# CDevBoard.net
KiCad netlist of a schematic drawn in EAGLE
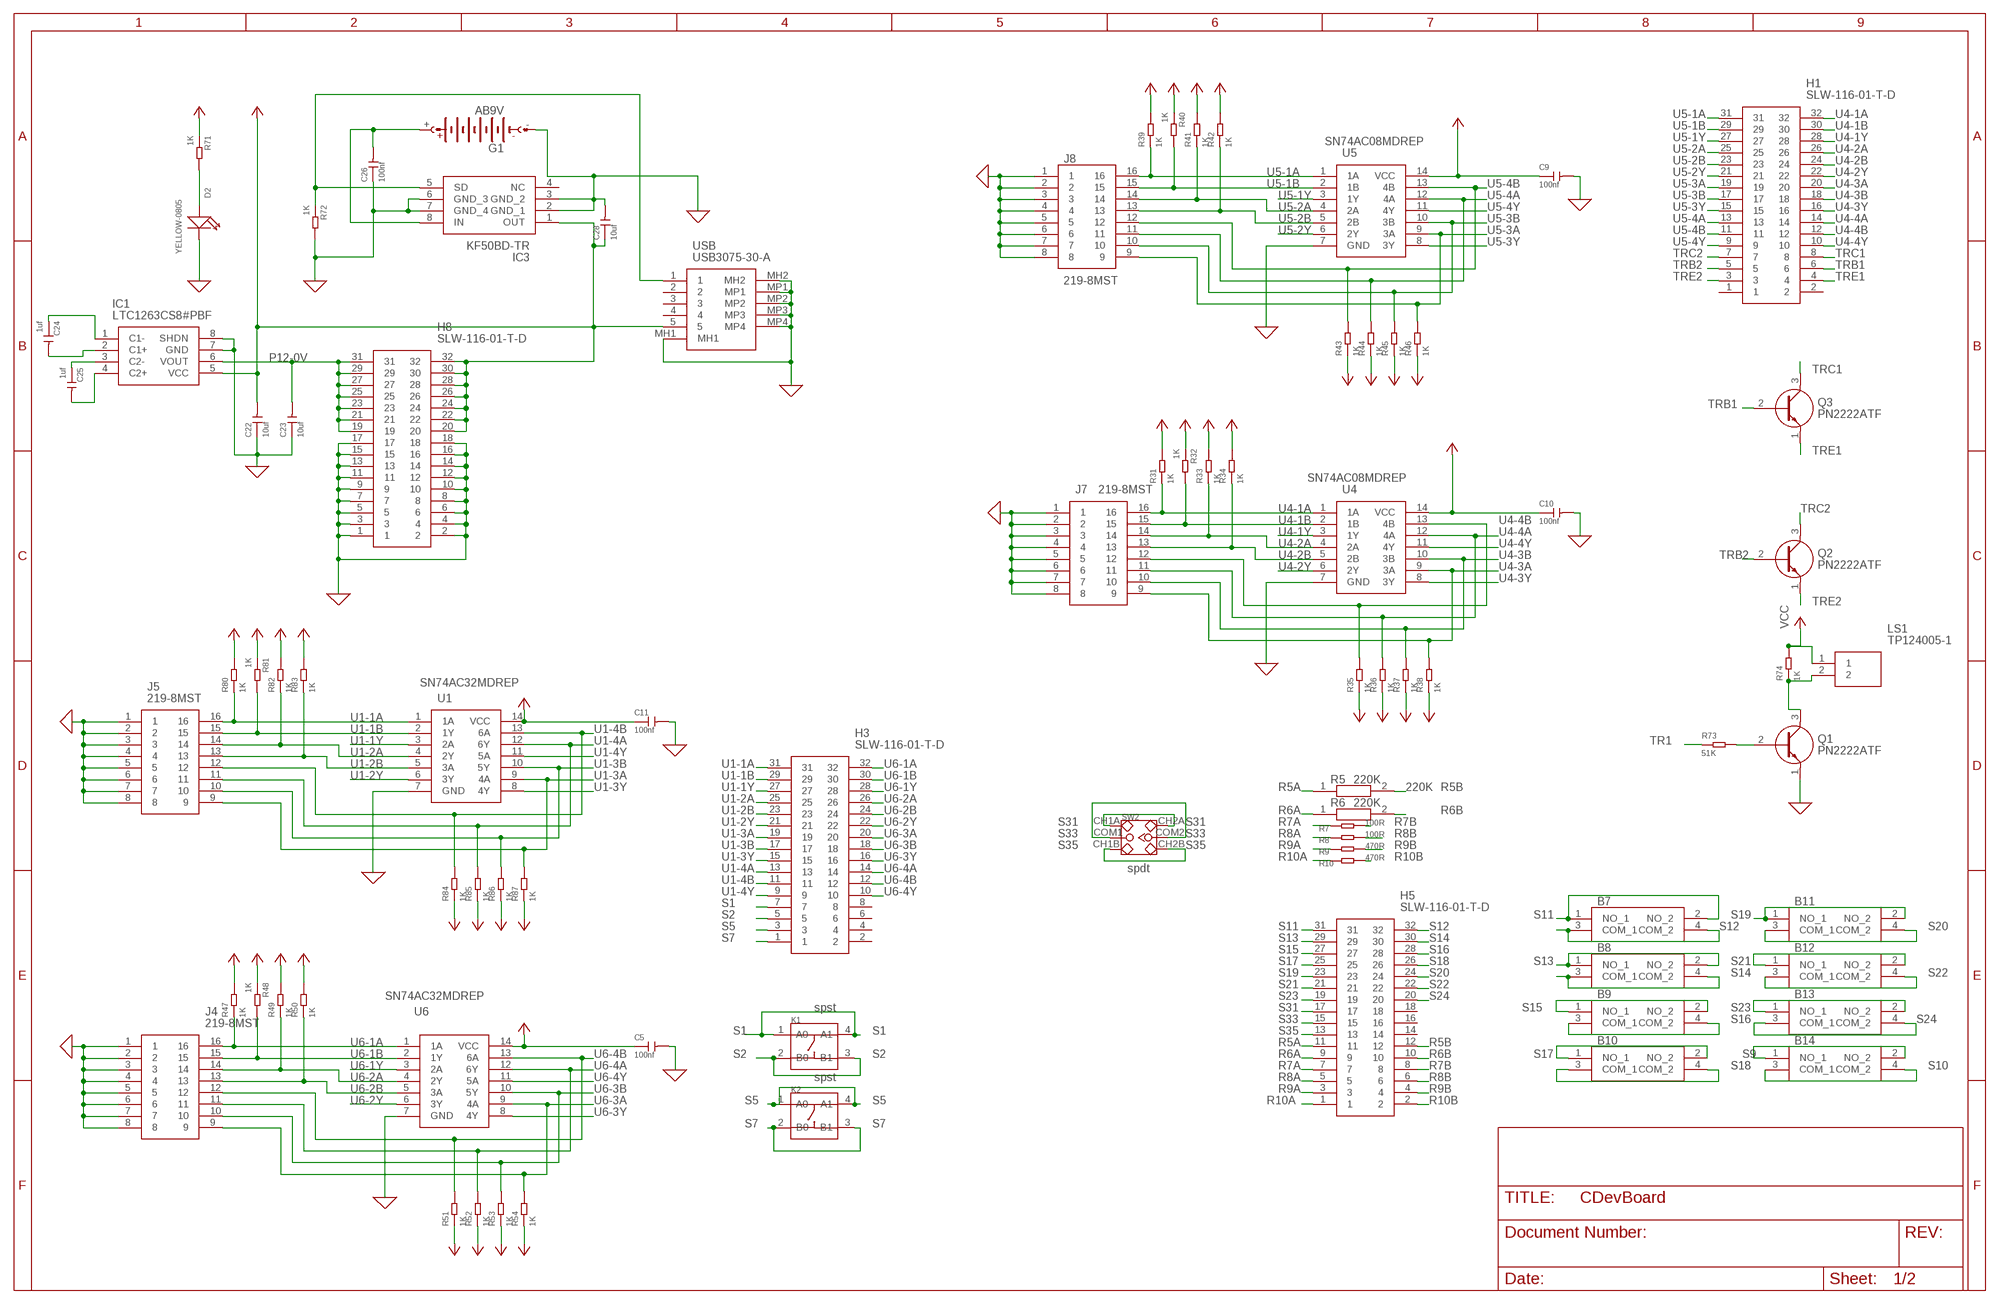
[diagram p0: schematic, sheet 1]
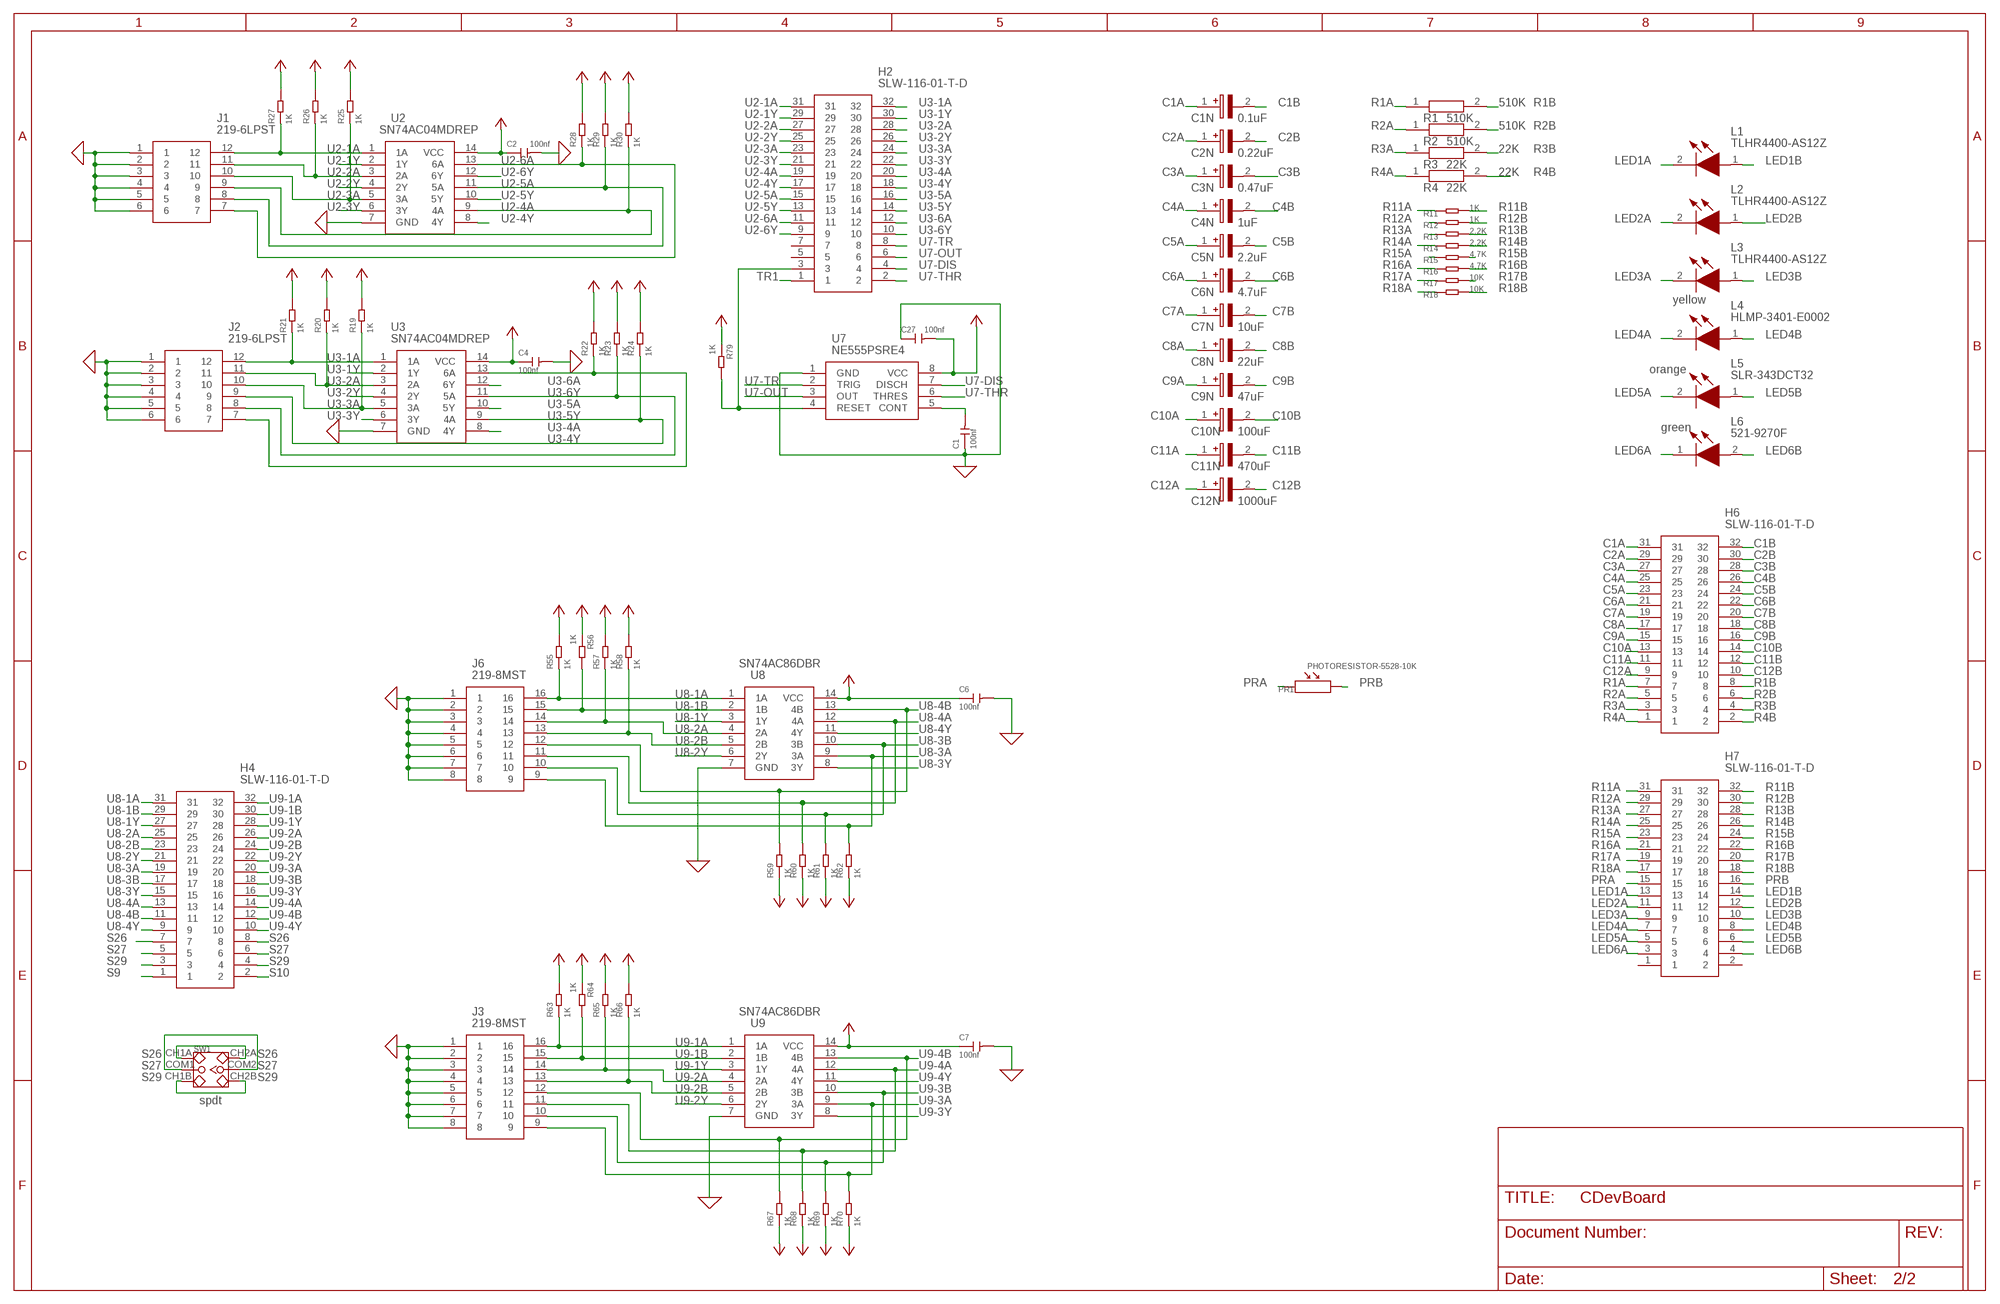
[diagram p1: schematic, sheet 2]

(export (version "E")
  (design (tool "Eeschema 10.0.6"))
  (components
    (comp (ref "B7")
      (value "1301.9317")
      (footprint "eagle-import:13019317")
      (fields (field (name "MOUSER_PART_NUMBER") "693-1301.9317"))
      (libsource (lib "eagle-import") (part "1301.9317"))
    )
    (comp (ref "B8")
      (value "1301.9317")
      (footprint "eagle-import:13019317")
      (fields (field (name "MOUSER_PART_NUMBER") "693-1301.9317"))
      (libsource (lib "eagle-import") (part "1301.9317"))
    )
    (comp (ref "B9")
      (value "1301.9317")
      (footprint "eagle-import:13019317")
      (fields (field (name "MOUSER_PART_NUMBER") "693-1301.9317"))
      (libsource (lib "eagle-import") (part "1301.9317"))
    )
    (comp (ref "B10")
      (value "1301.9317")
      (footprint "eagle-import:13019317")
      (fields (field (name "MOUSER_PART_NUMBER") "693-1301.9317"))
      (libsource (lib "eagle-import") (part "1301.9317"))
    )
    (comp (ref "B11")
      (value "1301.9317")
      (footprint "eagle-import:13019317")
      (fields (field (name "MOUSER_PART_NUMBER") "693-1301.9317"))
      (libsource (lib "eagle-import") (part "1301.9317"))
    )
    (comp (ref "B12")
      (value "1301.9317")
      (footprint "eagle-import:13019317")
      (fields (field (name "MOUSER_PART_NUMBER") "693-1301.9317"))
      (libsource (lib "eagle-import") (part "1301.9317"))
    )
    (comp (ref "B13")
      (value "1301.9317")
      (footprint "eagle-import:13019317")
      (fields (field (name "MOUSER_PART_NUMBER") "693-1301.9317"))
      (libsource (lib "eagle-import") (part "1301.9317"))
    )
    (comp (ref "B14")
      (value "1301.9317")
      (footprint "eagle-import:13019317")
      (fields (field (name "MOUSER_PART_NUMBER") "693-1301.9317"))
      (libsource (lib "eagle-import") (part "1301.9317"))
    )
    (comp (ref "C5")
      (value "100nf")
      (footprint "eagle-import:C0402")
      (fields (field (name "MPN") "CC0402KRX7R8BB104"))
      (libsource (lib "eagle-import") (part "CERAMIC-100NF-25V-10%-X7R(0402)"))
    )
    (comp (ref "C9")
      (value "100nf")
      (footprint "eagle-import:C0402")
      (fields (field (name "MPN") "CC0402KRX7R8BB104"))
      (libsource (lib "eagle-import") (part "CERAMIC-100NF-25V-10%-X7R(0402)"))
    )
    (comp (ref "C10")
      (value "100nf")
      (footprint "eagle-import:C0402")
      (fields (field (name "MPN") "CC0402KRX7R8BB104"))
      (libsource (lib "eagle-import") (part "CERAMIC-100NF-25V-10%-X7R(0402)"))
    )
    (comp (ref "C11")
      (value "100nf")
      (footprint "eagle-import:C0402")
      (fields (field (name "MPN") "CC0402KRX7R8BB104"))
      (libsource (lib "eagle-import") (part "CERAMIC-100NF-25V-10%-X7R(0402)"))
    )
    (comp (ref "C22")
      (value "10uf")
      (footprint "eagle-import:C0805")
      (fields (field (name "MPN") "CC0805KKX5R8BB106"))
      (libsource (lib "eagle-import") (part "CERAMIC-10UF-25V-10%-X5R(0805)"))
    )
    (comp (ref "C23")
      (value "10uf")
      (footprint "eagle-import:C0805")
      (fields (field (name "MPN") "CC0805KKX5R8BB106"))
      (libsource (lib "eagle-import") (part "CERAMIC-10UF-25V-10%-X5R(0805)"))
    )
    (comp (ref "C24")
      (value "1uf")
      (footprint "eagle-import:C0805")
      (fields (field (name "MPN") "CC0805KKX7R8BB105"))
      (libsource (lib "eagle-import") (part "CERAMIC-1UF-25V-10%-X7R(0805)"))
    )
    (comp (ref "C25")
      (value "1uf")
      (footprint "eagle-import:C0805")
      (fields (field (name "MPN") "CC0805KKX7R8BB105"))
      (libsource (lib "eagle-import") (part "CERAMIC-1UF-25V-10%-X7R(0805)"))
    )
    (comp (ref "C26")
      (value "100nf")
      (footprint "eagle-import:C0603")
      (fields (field (name "MPN") "CC0603KRX7R9BB104"))
      (libsource (lib "eagle-import") (part "CERAMIC-100NF-50V-10%-X7R(0603)"))
    )
    (comp (ref "C28")
      (value "10uf")
      (footprint "eagle-import:C0805")
      (fields (field (name "MPN") "CC0805KKX5R8BB106"))
      (libsource (lib "eagle-import") (part "CERAMIC-10UF-25V-10%-X5R(0805)"))
    )
    (comp (ref "D2")
      (value "YELLOW-0805")
      (footprint "eagle-import:LED-0805")
      (fields (field (name "MPN") "17-215UYC/S530-A3/TR8"))
      (libsource (lib "eagle-import") (part "SMD-LED-CLEAR-YELLOW(0805)"))
    )
    (comp (ref "G1")
      (value "AB9V")
      (footprint "eagle-import:AB9V")
      (libsource (lib "eagle-import") (part "AB9V"))
    )
    (comp (ref "H1")
      (value "SLW-116-01-T-D")
      (footprint "eagle-import:SLW-116-01-X")
      (fields (field (name "MOUSER_PART_NUMBER") "200-SLW11601TD"))
      (libsource (lib "eagle-import") (part "SLW-116-01-T-D"))
    )
    (comp (ref "H3")
      (value "SLW-116-01-T-D")
      (footprint "eagle-import:SLW-116-01-X")
      (fields (field (name "MOUSER_PART_NUMBER") "200-SLW11601TD"))
      (libsource (lib "eagle-import") (part "SLW-116-01-T-D"))
    )
    (comp (ref "H5")
      (value "SLW-116-01-T-D")
      (footprint "eagle-import:SLW-116-01-X")
      (fields (field (name "MOUSER_PART_NUMBER") "200-SLW11601TD"))
      (libsource (lib "eagle-import") (part "SLW-116-01-T-D"))
    )
    (comp (ref "H8")
      (value "SLW-116-01-T-D")
      (footprint "eagle-import:SLW-116-01-X")
      (fields (field (name "MOUSER_PART_NUMBER") "200-SLW11601TD"))
      (libsource (lib "eagle-import") (part "SLW-116-01-T-D"))
    )
    (comp (ref "IC1")
      (value "LTC1263CS8#PBF")
      (footprint "eagle-import:SOIC127P599X175-8N")
      (fields (field (name "MOUSER_PART_NUMBER") "584-LTC1263CS8#PBF"))
      (libsource (lib "eagle-import") (part "LTC1263CS8#PBF"))
    )
    (comp (ref "IC3")
      (value "KF50BD-TR")
      (footprint "eagle-import:SOIC127P600X175-8N")
      (description "ST Micro LDO Voltage Regulators 5.0V 0.5A Positive")
      (fields
        (field (name "MANUFACTURER_PART_NUMBER") "LM2936QHBMA-5.0/NOPB")
        (field (name "MOUSER_PART_NUMBER") "595-LM2936QHBMA50NPB")
        (field (name "MANUFACTURER_NAME") "ST Microelectronics")
        (field (name "MANUFACTURER_PART_NUMBER_1") "KF50BD-TR")
        (field (name "MOUSER_PART_NUMBER_1") "511-KF50BD-TR")
        (field (name "MOUSER_PRICE-STOCK") "https://www.mouser.com/ProductDetail/STMicroelectronics/KF50BD-TR?qs=sGAEpiMZZMt1hubY80%2Fs8BMSFdzaUFUoRpw27qJPtVo%3D")
      )
      (libsource (lib "eagle-import") (part "LM2936QHBMA-5.0_NOPB"))
    )
    (comp (ref "J4")
      (value "219-8MST")
      (footprint "eagle-import:2198MST")
      (fields (field (name "MOUSER_PART_NUMBER") "774-2198MST"))
      (libsource (lib "eagle-import") (part "219-8MST"))
    )
    (comp (ref "J5")
      (value "219-8MST")
      (footprint "eagle-import:2198MST")
      (fields (field (name "MOUSER_PART_NUMBER") "774-2198MST"))
      (libsource (lib "eagle-import") (part "219-8MST"))
    )
    (comp (ref "J7")
      (value "219-8MST")
      (footprint "eagle-import:2198MST")
      (fields (field (name "MOUSER_PART_NUMBER") "774-2198MST"))
      (libsource (lib "eagle-import") (part "219-8MST"))
    )
    (comp (ref "J8")
      (value "219-8MST")
      (footprint "eagle-import:2198MST")
      (fields (field (name "MOUSER_PART_NUMBER") "774-2198MST"))
      (libsource (lib "eagle-import") (part "219-8MST"))
    )
    (comp (ref "K1")
      (value "SMD-SWITCH-TACTILE-SPST-NO(4P-D6.0MM)")
      (footprint "eagle-import:SW4-SMD-6.0X6.0X5.0MM")
      (fields (field (name "MPN") "DTSM-62K-S-V-T/R(SN431)") (field (name "TYPE") "spst"))
      (libsource (lib "eagle-import") (part "SMD-SWITCH-TACTILE-SPST-NO(4P-D6.0MM)"))
    )
    (comp (ref "K2")
      (value "SMD-SWITCH-TACTILE-SPST-NO(4P-D6.0MM)")
      (footprint "eagle-import:SW4-SMD-6.0X6.0X5.0MM")
      (fields (field (name "MPN") "DTSM-62K-S-V-T/R(SN431)") (field (name "TYPE") "spst"))
      (libsource (lib "eagle-import") (part "SMD-SWITCH-TACTILE-SPST-NO(4P-D6.0MM)"))
    )
    (comp (ref "LS1")
      (value "TP124005-1")
      (footprint "eagle-import:TP1240051")
      (libsource (lib "eagle-import") (part "TP124005-1"))
    )
    (comp (ref "Q1")
      (value "PN2222ATF")
      (footprint "eagle-import:KA431AZTA")
      (fields (field (name "MOUSER_PART_NUMBER") "512-PN2222ATF"))
      (libsource (lib "eagle-import") (part "PN2222ATF"))
    )
    (comp (ref "Q2")
      (value "PN2222ATF")
      (footprint "eagle-import:KA431AZTA")
      (fields (field (name "MOUSER_PART_NUMBER") "512-PN2222ATF"))
      (libsource (lib "eagle-import") (part "PN2222ATF"))
    )
    (comp (ref "Q3")
      (value "PN2222ATF")
      (footprint "eagle-import:KA431AZTA")
      (fields (field (name "MOUSER_PART_NUMBER") "512-PN2222ATF"))
      (libsource (lib "eagle-import") (part "PN2222ATF"))
    )
    (comp (ref "R5")
      (value "220K")
      (footprint "eagle-import:RESAD1590W60L630D240")
      (fields
        (field (name "MANUFACTURER_PART_NUMBER") "CFR-25JR-52-100R")
        (field (name "MOUSER_PART_NUMBER") "603-CFR-25JR-52100R")
        (field (name "MOUSER_PRICE-STOCK") "https://www.mouser.com/ProductDetail/Yageo/CFR-25JR-52-220K?qs=%2Fha2pyFaduiUclxQMvctpADd0RPeGi7tTMMkrHXtLPwiTqRb%252BoIJFg%3D%3D")
        (field (name "VAL") "220K")
      )
      (libsource (lib "eagle-import") (part "CFR-NEW_CFR-25JR-52-100R"))
    )
    (comp (ref "R6")
      (value "220K")
      (footprint "eagle-import:RESAD1590W60L630D240")
      (fields
        (field (name "MANUFACTURER_PART_NUMBER") "CFR-25JR-52-100R")
        (field (name "MOUSER_PART_NUMBER") "603-CFR-25JR-52100R")
        (field (name "MANUFACTURER_PART_NUMBER_1") "CFR-25JR-52100R")
        (field (name "MOUSER_PRICE-STOCK") "https://www.mouser.com/ProductDetail/Yageo/CFR-25JR-52-220K?qs=%2Fha2pyFaduiUclxQMvctpADd0RPeGi7tTMMkrHXtLPwiTqRb%252BoIJFg%3D%3D")
      )
      (libsource (lib "eagle-import") (part "CFR-25JR-52-100R"))
    )
    (comp (ref "R7")
      (value "100R")
      (footprint "eagle-import:PR-D2.3XL6.5MM")
      (fields (field (name "MPN") "FHCFR-1/4W-101J"))
      (libsource (lib "eagle-import") (part "DIP-RES-100R-5%-1/4W(PR-D2.3XL6.5MM)"))
    )
    (comp (ref "R8")
      (value "100R")
      (footprint "eagle-import:PR-D2.3XL6.5MM")
      (fields (field (name "MPN") "FHCFR-1/4W-101J"))
      (libsource (lib "eagle-import") (part "DIP-RES-100R-5%-1/4W(PR-D2.3XL6.5MM)"))
    )
    (comp (ref "R9")
      (value "470R")
      (footprint "eagle-import:PR-D2.3XL6.5MM")
      (fields (field (name "MPN") "FHCFR-1/4W-471J"))
      (libsource (lib "eagle-import") (part "DIP-RES-470R-5%-1/4W(PR-D2.3XL6.5MM)"))
    )
    (comp (ref "R10")
      (value "470R")
      (footprint "eagle-import:PR-D2.3XL6.5MM")
      (fields (field (name "MPN") "FHCFR-1/4W-471J"))
      (libsource (lib "eagle-import") (part "DIP-RES-470R-5%-1/4W(PR-D2.3XL6.5MM)"))
    )
    (comp (ref "R31")
      (value "1K")
      (footprint "eagle-import:R0805")
      (fields (field (name "MPN") "RC0805JR-071KL"))
      (libsource (lib "eagle-import") (part "SMD-RES-5.1K-1%-1/8W(0805)"))
    )
    (comp (ref "R32")
      (value "1K")
      (footprint "eagle-import:R0805")
      (fields (field (name "MPN") "RC0805JR-071KL"))
      (libsource (lib "eagle-import") (part "SMD-RES-5.1K-1%-1/8W(0805)"))
    )
    (comp (ref "R33")
      (value "1K")
      (footprint "eagle-import:R0805")
      (fields (field (name "MPN") "RC0805JR-071KL"))
      (libsource (lib "eagle-import") (part "SMD-RES-5.1K-1%-1/8W(0805)"))
    )
    (comp (ref "R34")
      (value "1K")
      (footprint "eagle-import:R0805")
      (fields (field (name "MPN") "RC0805JR-071KL"))
      (libsource (lib "eagle-import") (part "SMD-RES-5.1K-1%-1/8W(0805)"))
    )
    (comp (ref "R35")
      (value "1K")
      (footprint "eagle-import:R0805")
      (fields (field (name "MPN") "RC0805JR-071KL"))
      (libsource (lib "eagle-import") (part "SMD-RES-5.1K-1%-1/8W(0805)"))
    )
    (comp (ref "R36")
      (value "1K")
      (footprint "eagle-import:R0805")
      (fields (field (name "MPN") "RC0805JR-071KL"))
      (libsource (lib "eagle-import") (part "SMD-RES-5.1K-1%-1/8W(0805)"))
    )
    (comp (ref "R37")
      (value "1K")
      (footprint "eagle-import:R0805")
      (fields (field (name "MPN") "RC0805JR-071KL"))
      (libsource (lib "eagle-import") (part "SMD-RES-5.1K-1%-1/8W(0805)"))
    )
    (comp (ref "R38")
      (value "1K")
      (footprint "eagle-import:R0805")
      (fields (field (name "MPN") "RC0805JR-071KL"))
      (libsource (lib "eagle-import") (part "SMD-RES-5.1K-1%-1/8W(0805)"))
    )
    (comp (ref "R39")
      (value "1K")
      (footprint "eagle-import:R0805")
      (fields (field (name "MPN") "RC0805JR-071KL"))
      (libsource (lib "eagle-import") (part "SMD-RES-5.1K-1%-1/8W(0805)"))
    )
    (comp (ref "R40")
      (value "1K")
      (footprint "eagle-import:R0805")
      (fields (field (name "MPN") "RC0805JR-071KL"))
      (libsource (lib "eagle-import") (part "SMD-RES-5.1K-1%-1/8W(0805)"))
    )
    (comp (ref "R41")
      (value "1K")
      (footprint "eagle-import:R0805")
      (fields (field (name "MPN") "RC0805JR-071KL"))
      (libsource (lib "eagle-import") (part "SMD-RES-5.1K-1%-1/8W(0805)"))
    )
    (comp (ref "R42")
      (value "1K")
      (footprint "eagle-import:R0805")
      (fields (field (name "MPN") "RC0805JR-071KL"))
      (libsource (lib "eagle-import") (part "SMD-RES-5.1K-1%-1/8W(0805)"))
    )
    (comp (ref "R43")
      (value "1K")
      (footprint "eagle-import:R0805")
      (fields (field (name "MPN") "RC0805JR-071KL"))
      (libsource (lib "eagle-import") (part "SMD-RES-5.1K-1%-1/8W(0805)"))
    )
    (comp (ref "R44")
      (value "1K")
      (footprint "eagle-import:R0805")
      (fields (field (name "MPN") "RC0805JR-071KL"))
      (libsource (lib "eagle-import") (part "SMD-RES-5.1K-1%-1/8W(0805)"))
    )
    (comp (ref "R45")
      (value "1K")
      (footprint "eagle-import:R0805")
      (fields (field (name "MPN") "RC0805JR-071KL"))
      (libsource (lib "eagle-import") (part "SMD-RES-5.1K-1%-1/8W(0805)"))
    )
    (comp (ref "R46")
      (value "1K")
      (footprint "eagle-import:R0805")
      (fields (field (name "MPN") "RC0805JR-071KL"))
      (libsource (lib "eagle-import") (part "SMD-RES-5.1K-1%-1/8W(0805)"))
    )
    (comp (ref "R47")
      (value "1K")
      (footprint "eagle-import:R0805")
      (fields (field (name "MPN") "RC0805JR-071KL"))
      (libsource (lib "eagle-import") (part "SMD-RES-5.1K-1%-1/8W(0805)"))
    )
    (comp (ref "R48")
      (value "1K")
      (footprint "eagle-import:R0805")
      (fields (field (name "MPN") "RC0805JR-071KL"))
      (libsource (lib "eagle-import") (part "SMD-RES-5.1K-1%-1/8W(0805)"))
    )
    (comp (ref "R49")
      (value "1K")
      (footprint "eagle-import:R0805")
      (fields (field (name "MPN") "RC0805JR-071KL"))
      (libsource (lib "eagle-import") (part "SMD-RES-5.1K-1%-1/8W(0805)"))
    )
    (comp (ref "R50")
      (value "1K")
      (footprint "eagle-import:R0805")
      (fields (field (name "MPN") "RC0805JR-071KL"))
      (libsource (lib "eagle-import") (part "SMD-RES-5.1K-1%-1/8W(0805)"))
    )
    (comp (ref "R51")
      (value "1K")
      (footprint "eagle-import:R0805")
      (fields (field (name "MPN") "RC0805JR-071KL"))
      (libsource (lib "eagle-import") (part "SMD-RES-5.1K-1%-1/8W(0805)"))
    )
    (comp (ref "R52")
      (value "1K")
      (footprint "eagle-import:R0805")
      (fields (field (name "MPN") "RC0805JR-071KL"))
      (libsource (lib "eagle-import") (part "SMD-RES-5.1K-1%-1/8W(0805)"))
    )
    (comp (ref "R53")
      (value "1K")
      (footprint "eagle-import:R0805")
      (fields (field (name "MPN") "RC0805JR-071KL"))
      (libsource (lib "eagle-import") (part "SMD-RES-5.1K-1%-1/8W(0805)"))
    )
    (comp (ref "R54")
      (value "1K")
      (footprint "eagle-import:R0805")
      (fields (field (name "MPN") "RC0805JR-071KL"))
      (libsource (lib "eagle-import") (part "SMD-RES-5.1K-1%-1/8W(0805)"))
    )
    (comp (ref "R71")
      (value "1K")
      (footprint "eagle-import:R0805")
      (fields (field (name "MPN") "RC0805JR-071KL"))
      (libsource (lib "eagle-import") (part "SMD-RES-200R-1%-1/8W(0805)"))
    )
    (comp (ref "R72")
      (value "1K")
      (footprint "eagle-import:R0805")
      (fields (field (name "MPN") "RC0805JR-071KL"))
      (libsource (lib "eagle-import") (part "SMD-RES-5.1K-1%-1/8W(0805)"))
    )
    (comp (ref "R73")
      (value "51K")
      (footprint "eagle-import:R0603")
      (fields (field (name "MPN") "RC0603FR-071K5L"))
      (libsource (lib "eagle-import") (part "SMD-RES-51K-1%-1/10W(0603)"))
    )
    (comp (ref "R74")
      (value "1K")
      (footprint "eagle-import:R0805")
      (fields (field (name "MPN") "RC0805JR-071KL"))
      (libsource (lib "eagle-import") (part "SMD-RES-1K-1%-1/8W(0805)"))
    )
    (comp (ref "R80")
      (value "1K")
      (footprint "eagle-import:R0805")
      (fields (field (name "MPN") "RC0805JR-071KL"))
      (libsource (lib "eagle-import") (part "SMD-RES-5.1K-1%-1/8W(0805)"))
    )
    (comp (ref "R81")
      (value "1K")
      (footprint "eagle-import:R0805")
      (fields (field (name "MPN") "RC0805JR-071KL"))
      (libsource (lib "eagle-import") (part "SMD-RES-5.1K-1%-1/8W(0805)"))
    )
    (comp (ref "R82")
      (value "1K")
      (footprint "eagle-import:R0805")
      (fields (field (name "MPN") "RC0805JR-071KL"))
      (libsource (lib "eagle-import") (part "SMD-RES-5.1K-1%-1/8W(0805)"))
    )
    (comp (ref "R83")
      (value "1K")
      (footprint "eagle-import:R0805")
      (fields (field (name "MPN") "RC0805JR-071KL"))
      (libsource (lib "eagle-import") (part "SMD-RES-5.1K-1%-1/8W(0805)"))
    )
    (comp (ref "R84")
      (value "1K")
      (footprint "eagle-import:R0805")
      (fields (field (name "MPN") "RC0805JR-071KL"))
      (libsource (lib "eagle-import") (part "SMD-RES-5.1K-1%-1/8W(0805)"))
    )
    (comp (ref "R85")
      (value "1K")
      (footprint "eagle-import:R0805")
      (fields (field (name "MPN") "RC0805JR-071KL"))
      (libsource (lib "eagle-import") (part "SMD-RES-5.1K-1%-1/8W(0805)"))
    )
    (comp (ref "R86")
      (value "1K")
      (footprint "eagle-import:R0805")
      (fields (field (name "MPN") "RC0805JR-071KL"))
      (libsource (lib "eagle-import") (part "SMD-RES-5.1K-1%-1/8W(0805)"))
    )
    (comp (ref "R87")
      (value "1K")
      (footprint "eagle-import:R0805")
      (fields (field (name "MPN") "RC0805JR-071KL"))
      (libsource (lib "eagle-import") (part "SMD-RES-5.1K-1%-1/8W(0805)"))
    )
    (comp (ref "SW2")
      (value "DIP-TOGGLE-SWITCH-2CH-(2X3P-2.54)")
      (footprint "eagle-import:SW6-2.54-9.0X3.5X3.2+2.0MM")
      (fields (field (name "MPN") "MS-22D18 G2 ROHS") (field (name "TYPE") "spdt"))
      (libsource (lib "eagle-import") (part "DIP-TOGGLE-SWITCH-2CH-(2X3P-2.54)"))
    )
    (comp (ref "U1")
      (value "SN74AC04MDREP")
      (footprint "eagle-import:SOIC127P600X175-14N")
      (fields
        (field (name "MOUSER_PART_NUMBER") "595-SN74AC04MDREP")
        (field (name "MANUFACTURER_PART_NUMBER") "SN74AC32MDREP")
        (field (name "VAL") "SN74AC32MDREP")
      )
      (libsource (lib "eagle-import") (part "SN74AC04MDREP"))
    )
    (comp (ref "U4")
      (value "SN74AC08MDREP")
      (footprint "eagle-import:SOIC127P600X175-14N")
      (fields (field (name "MOUSER_PART_NUMBER") "595-SN74AC08MDREP"))
      (libsource (lib "eagle-import") (part "SN74AC08MDREP"))
    )
    (comp (ref "U5")
      (value "SN74AC08MDREP")
      (footprint "eagle-import:SOIC127P600X175-14N")
      (fields (field (name "MOUSER_PART_NUMBER") "595-SN74AC08MDREP"))
      (libsource (lib "eagle-import") (part "SN74AC08MDREP"))
    )
    (comp (ref "U6")
      (value "SN74AC04MDREP")
      (footprint "eagle-import:SOIC127P600X175-14N")
      (fields
        (field (name "MOUSER_PART_NUMBER") "595-SN74AC04MDREP")
        (field (name "MANUFACTURER_PART_NUMBER") "SN74AC32MDREP")
        (field (name "VAL") "SN74AC32MDREP")
      )
      (libsource (lib "eagle-import") (part "SN74AC04MDREP"))
    )
    (comp (ref "USB")
      (value "USB3075-30-A")
      (footprint "eagle-import:USB307530A")
      (fields (field (name "MOUSER_PART_NUMBER") "640-USB3075-30-A"))
      (libsource (lib "eagle-import") (part "USB3075-30-A"))
    )
    (comp (ref "C1")
      (value "100nf")
      (footprint "eagle-import:C0402")
      (fields (field (name "MPN") "CC0402KRX7R8BB104"))
      (libsource (lib "eagle-import") (part "CERAMIC-100NF-25V-10%-X7R(0402)"))
    )
    (comp (ref "C1N")
      (value "0.1uF")
      (footprint "eagle-import:CAPPRD200W52D500H1250")
      (fields
        (field (name "MANUFACTURER_PART_NUMBER") "860010672001")
        (field (name "MOUSER_PART_NUMBER") "710-860010672001")
      )
      (libsource (lib "eagle-import") (part "860010672001"))
    )
    (comp (ref "C2")
      (value "100nf")
      (footprint "eagle-import:C0402")
      (fields (field (name "MPN") "CC0402KRX7R8BB104"))
      (libsource (lib "eagle-import") (part "CERAMIC-100NF-25V-10%-X7R(0402)"))
    )
    (comp (ref "C2N")
      (value "0.22uF")
      (footprint "eagle-import:CAPPRD200W52D500H1250")
      (fields
        (field (name "MANUFACTURER_PART_NUMBER") "860010672001")
        (field (name "MOUSER_PART_NUMBER") "710-860010672001")
      )
      (libsource (lib "eagle-import") (part "860010672001"))
    )
    (comp (ref "C3N")
      (value "0.47uF")
      (footprint "eagle-import:CAPPRD200W52D500H1250")
      (fields
        (field (name "MANUFACTURER_PART_NUMBER") "860010672001")
        (field (name "MOUSER_PART_NUMBER") "710-860010672001")
      )
      (libsource (lib "eagle-import") (part "860010672001"))
    )
    (comp (ref "C4")
      (value "100nf")
      (footprint "eagle-import:C0402")
      (fields (field (name "MPN") "CC0402KRX7R8BB104"))
      (libsource (lib "eagle-import") (part "CERAMIC-100NF-25V-10%-X7R(0402)"))
    )
    (comp (ref "C4N")
      (value "1uF")
      (footprint "eagle-import:CAPPRD200W52D500H1250")
      (fields
        (field (name "MANUFACTURER_PART_NUMBER") "860010672001")
        (field (name "MOUSER_PART_NUMBER") "710-860010672001")
      )
      (libsource (lib "eagle-import") (part "860010672001"))
    )
    (comp (ref "C5N")
      (value "2.2uF")
      (footprint "eagle-import:CAPPRD200W52D500H1250")
      (fields
        (field (name "MANUFACTURER_PART_NUMBER") "860020672006")
        (field (name "MOUSER_PART_NUMBER") "710-860020672006")
      )
      (libsource (lib "eagle-import") (part "860020672006"))
    )
    (comp (ref "C6")
      (value "100nf")
      (footprint "eagle-import:C0402")
      (fields (field (name "MPN") "CC0402KRX7R8BB104"))
      (libsource (lib "eagle-import") (part "CERAMIC-100NF-25V-10%-X7R(0402)"))
    )
    (comp (ref "C6N")
      (value "4.7uF")
      (footprint "eagle-import:CAPPRD200W52D500H1250")
      (fields
        (field (name "MANUFACTURER_PART_NUMBER") "860020672006")
        (field (name "MOUSER_PART_NUMBER") "710-860020672006")
      )
      (libsource (lib "eagle-import") (part "860020672006"))
    )
    (comp (ref "C7")
      (value "100nf")
      (footprint "eagle-import:C0402")
      (fields (field (name "MPN") "CC0402KRX7R8BB104"))
      (libsource (lib "eagle-import") (part "CERAMIC-100NF-25V-10%-X7R(0402)"))
    )
    (comp (ref "C7N")
      (value "10uF")
      (footprint "eagle-import:CAPPRD200W50D500H1250")
      (fields
        (field (name "MANUFACTURER_PART_NUMBER") "ESK106M010AC3AA")
        (field (name "MOUSER_PART_NUMBER") "80-ESK106M010AC3AA")
      )
      (libsource (lib "eagle-import") (part "ESK106M010AC3AA"))
    )
    (comp (ref "C8N")
      (value "22uF")
      (footprint "eagle-import:CAPPRD200W52D500H1250")
      (fields (field (name "MANUFACTURER_PART_NUMBER") "860010272003") (field (name "VAL") "22uF"))
      (libsource (lib "eagle-import") (part "860010272003"))
    )
    (comp (ref "C9N")
      (value "47uF")
      (footprint "eagle-import:CAPPRD200W52D500H1250")
      (fields (field (name "MANUFACTURER_PART_NUMBER") "860010272003") (field (name "VAL") "47uF"))
      (libsource (lib "eagle-import") (part "860010272003"))
    )
    (comp (ref "C10N")
      (value "100uF")
      (footprint "eagle-import:CAPPRD200W52D500H1250")
      (fields (field (name "MANUFACTURER_PART_NUMBER") "860010272003"))
      (libsource (lib "eagle-import") (part "860010272003"))
    )
    (comp (ref "C11N")
      (value "470uF")
      (footprint "eagle-import:CAPPRD200W52D500H1250")
      (fields (field (name "MANUFACTURER_PART_NUMBER") "860010272003"))
      (libsource (lib "eagle-import") (part "860010272003"))
    )
    (comp (ref "C12N")
      (value "1000uF")
      (footprint "eagle-import:CAPPRD200W52D500H1250")
      (fields (field (name "MANUFACTURER_PART_NUMBER") "860010272003"))
      (libsource (lib "eagle-import") (part "860010272003"))
    )
    (comp (ref "C27")
      (value "100nf")
      (footprint "eagle-import:C0402")
      (fields (field (name "MPN") "CC0402KRX7R8BB104"))
      (libsource (lib "eagle-import") (part "CERAMIC-100NF-25V-10%-X7R(0402)"))
    )
    (comp (ref "H2")
      (value "SLW-116-01-T-D")
      (footprint "eagle-import:SLW-116-01-X")
      (fields (field (name "MOUSER_PART_NUMBER") "200-SLW11601TD"))
      (libsource (lib "eagle-import") (part "SLW-116-01-T-D"))
    )
    (comp (ref "H4")
      (value "SLW-116-01-T-D")
      (footprint "eagle-import:SLW-116-01-X")
      (fields (field (name "MOUSER_PART_NUMBER") "200-SLW11601TD"))
      (libsource (lib "eagle-import") (part "SLW-116-01-T-D"))
    )
    (comp (ref "H6")
      (value "SLW-116-01-T-D")
      (footprint "eagle-import:SLW-116-01-X")
      (fields (field (name "MOUSER_PART_NUMBER") "200-SLW11601TD"))
      (libsource (lib "eagle-import") (part "SLW-116-01-T-D"))
    )
    (comp (ref "H7")
      (value "SLW-116-01-T-D")
      (footprint "eagle-import:SLW-116-01-X")
      (fields (field (name "MOUSER_PART_NUMBER") "200-SLW11601TD"))
      (libsource (lib "eagle-import") (part "SLW-116-01-T-D"))
    )
    (comp (ref "J1")
      (value "219-6LPST")
      (footprint "eagle-import:2196LPST")
      (fields (field (name "MOUSER_PART_NUMBER") "774-2196LPST"))
      (libsource (lib "eagle-import") (part "219-6LPST"))
    )
    (comp (ref "J2")
      (value "219-6LPST")
      (footprint "eagle-import:2196LPST")
      (fields (field (name "MOUSER_PART_NUMBER") "774-2196LPST"))
      (libsource (lib "eagle-import") (part "219-6LPST"))
    )
    (comp (ref "J3")
      (value "219-8MST")
      (footprint "eagle-import:2198MST")
      (fields (field (name "MOUSER_PART_NUMBER") "774-2198MST"))
      (libsource (lib "eagle-import") (part "219-8MST"))
    )
    (comp (ref "J6")
      (value "219-8MST")
      (footprint "eagle-import:2198MST")
      (fields (field (name "MOUSER_PART_NUMBER") "774-2198MST"))
      (libsource (lib "eagle-import") (part "219-8MST"))
    )
    (comp (ref "L1")
      (value "TLHR4400-AS12Z")
      (footprint "eagle-import:TLHR4400AS12Z")
      (fields (field (name "MOUSER_PART_NUMBER") "78-TLHR4400-AS12Z"))
      (libsource (lib "eagle-import") (part "TLHR4400-AS12Z"))
    )
    (comp (ref "L2")
      (value "TLHR4400-AS12Z")
      (footprint "eagle-import:TLHR4400AS12Z")
      (fields (field (name "MOUSER_PART_NUMBER") "78-TLHR4400-AS12Z"))
      (libsource (lib "eagle-import") (part "TLHR4400-AS12Z"))
    )
    (comp (ref "L3")
      (value "TLHR4400-AS12Z")
      (footprint "eagle-import:TLHR4400AS12Z")
      (fields (field (name "MOUSER_PART_NUMBER") "78-TLHR4400-AS12Z"))
      (libsource (lib "eagle-import") (part "TLHR4400-AS12Z"))
    )
    (comp (ref "L4")
      (value "HLMP-3401-E0002")
      (footprint "eagle-import:HLMP3401E0002")
      (fields (field (name "MOUSER_PART_NUMBER") "630-HLMP-3401-E0002") (field (name "COL") "yellow"))
      (libsource (lib "eagle-import") (part "HLMP-3401-E0002"))
    )
    (comp (ref "L5")
      (value "SLR-343DCT32")
      (footprint "eagle-import:SLR343DCT32")
      (fields (field (name "MOUSER_PART_NUMBER") "755-SLR-343DCT32") (field (name "COL") "orange"))
      (libsource (lib "eagle-import") (part "SLR-343DCT32"))
    )
    (comp (ref "L6")
      (value "521-9270F")
      (footprint "eagle-import:5219270F")
      (fields (field (name "MOUSER_PART_NUMBER") "645-521-9270F") (field (name "COL") "green"))
      (libsource (lib "eagle-import") (part "521-9270F"))
    )
    (comp (ref "PR1")
      (value "PHOTORESISTOR-5528-10K")
      (footprint "eagle-import:SNR2-3.0")
      (libsource (lib "eagle-import") (part "PHOTORESISTOR-5528-10K(2P-5.0X4.2MM)"))
    )
    (comp (ref "R1")
      (value "510K")
      (footprint "eagle-import:RESAD1590W60L630D240")
      (fields
        (field (name "MANUFACTURER_PART_NUMBER") "CFR-25JR-52-100R")
        (field (name "MOUSER_PART_NUMBER") "603-CFR-25JR-52100R")
        (field (name "VAL") "510K")
      )
      (libsource (lib "eagle-import") (part "CFR-25JR-52-100R"))
    )
    (comp (ref "R2")
      (value "510K")
      (footprint "eagle-import:RESAD1590W60L630D240")
      (fields
        (field (name "MANUFACTURER_PART_NUMBER") "CFR-25JR-52-100R")
        (field (name "MOUSER_PART_NUMBER") "603-CFR-25JR-52100R")
        (field (name "VAL") "510K")
      )
      (libsource (lib "eagle-import") (part "CFR-25JR-52-100R"))
    )
    (comp (ref "R3")
      (value "22K")
      (footprint "eagle-import:RESAD1590W60L630D240")
      (fields
        (field (name "MANUFACTURER_PART_NUMBER") "CFR-25JR-52-100R")
        (field (name "MOUSER_PART_NUMBER") "603-CFR-25JR-52100R")
        (field (name "VAL") "22K")
      )
      (libsource (lib "eagle-import") (part "CFR-25JR-52-100R"))
    )
    (comp (ref "R4")
      (value "22K")
      (footprint "eagle-import:RESAD1590W60L630D240")
      (fields
        (field (name "MANUFACTURER_PART_NUMBER") "CFR-25JR-52-100R")
        (field (name "MOUSER_PART_NUMBER") "603-CFR-25JR-52100R")
        (field (name "VAL") "22K")
      )
      (libsource (lib "eagle-import") (part "CFR-25JR-52-100R"))
    )
    (comp (ref "R11")
      (value "1K")
      (footprint "eagle-import:PR-D2.3XL6.5MM")
      (fields (field (name "MPN") "FHCFR-1/4W-102J"))
      (libsource (lib "eagle-import") (part "DIP-RES-1K-5%-1/4W(PR-D2.3XL6.5MM)"))
    )
    (comp (ref "R12")
      (value "1K")
      (footprint "eagle-import:PR-D2.3XL6.5MM")
      (fields (field (name "MPN") "FHCFR-1/4W-102J"))
      (libsource (lib "eagle-import") (part "DIP-RES-1K-5%-1/4W(PR-D2.3XL6.5MM)"))
    )
    (comp (ref "R13")
      (value "2.2K")
      (footprint "eagle-import:PR-D2.3XL6.5MM")
      (fields (field (name "MPN") "FHCFR-1/4W-222J"))
      (libsource (lib "eagle-import") (part "DIP-RES-2.2K-5%-1/4W(PR-D2.3XL6.5MM)"))
    )
    (comp (ref "R14")
      (value "2.2K")
      (footprint "eagle-import:PR-D2.3XL6.5MM")
      (fields (field (name "MPN") "FHCFR-1/4W-222J"))
      (libsource (lib "eagle-import") (part "DIP-RES-2.2K-5%-1/4W(PR-D2.3XL6.5MM)"))
    )
    (comp (ref "R15")
      (value "4.7K")
      (footprint "eagle-import:PR-D2.3XL6.5MM")
      (fields (field (name "MPN") "FHCFR-1/4W-472J"))
      (libsource (lib "eagle-import") (part "DIP-RES-4.7K-5%-1/4W(PR-D2.3XL6.5MM)"))
    )
    (comp (ref "R16")
      (value "4.7K")
      (footprint "eagle-import:PR-D2.3XL6.5MM")
      (fields (field (name "MPN") "FHCFR-1/4W-472J"))
      (libsource (lib "eagle-import") (part "DIP-RES-4.7K-5%-1/4W(PR-D2.3XL6.5MM)"))
    )
    (comp (ref "R17")
      (value "10K")
      (footprint "eagle-import:PR-D2.3XL6.5MM")
      (fields (field (name "MPN") "FHCFR-1/4W-103J"))
      (libsource (lib "eagle-import") (part "DIP-RES-10K-5%-1/4W(PR-D2.3XL6.5MM)"))
    )
    (comp (ref "R18")
      (value "10K")
      (footprint "eagle-import:PR-D2.3XL6.5MM")
      (fields (field (name "MPN") "FHCFR-1/4W-103J"))
      (libsource (lib "eagle-import") (part "DIP-RES-10K-5%-1/4W(PR-D2.3XL6.5MM)"))
    )
    (comp (ref "R19")
      (value "1K")
      (footprint "eagle-import:R0805")
      (fields (field (name "MPN") "RC0805JR-071KL"))
      (libsource (lib "eagle-import") (part "SMD-RES-5.1K-1%-1/8W(0805)"))
    )
    (comp (ref "R20")
      (value "1K")
      (footprint "eagle-import:R0805")
      (fields (field (name "MPN") "RC0805JR-071KL"))
      (libsource (lib "eagle-import") (part "SMD-RES-5.1K-1%-1/8W(0805)"))
    )
    (comp (ref "R21")
      (value "1K")
      (footprint "eagle-import:R0805")
      (fields (field (name "MPN") "RC0805JR-071KL"))
      (libsource (lib "eagle-import") (part "SMD-RES-5.1K-1%-1/8W(0805)"))
    )
    (comp (ref "R22")
      (value "1K")
      (footprint "eagle-import:R0805")
      (fields (field (name "MPN") "RC0805JR-071KL"))
      (libsource (lib "eagle-import") (part "SMD-RES-5.1K-1%-1/8W(0805)"))
    )
    (comp (ref "R23")
      (value "1K")
      (footprint "eagle-import:R0805")
      (fields (field (name "MPN") "RC0805JR-071KL"))
      (libsource (lib "eagle-import") (part "SMD-RES-5.1K-1%-1/8W(0805)"))
    )
    (comp (ref "R24")
      (value "1K")
      (footprint "eagle-import:R0805")
      (fields (field (name "MPN") "RC0805JR-071KL"))
      (libsource (lib "eagle-import") (part "SMD-RES-5.1K-1%-1/8W(0805)"))
    )
    (comp (ref "R25")
      (value "1K")
      (footprint "eagle-import:R0805")
      (fields (field (name "MPN") "RC0805JR-071KL"))
      (libsource (lib "eagle-import") (part "SMD-RES-5.1K-1%-1/8W(0805)"))
    )
    (comp (ref "R26")
      (value "1K")
      (footprint "eagle-import:R0805")
      (fields (field (name "MPN") "RC0805JR-071KL"))
      (libsource (lib "eagle-import") (part "SMD-RES-5.1K-1%-1/8W(0805)"))
    )
    (comp (ref "R27")
      (value "1K")
      (footprint "eagle-import:R0805")
      (fields (field (name "MPN") "RC0805JR-071KL"))
      (libsource (lib "eagle-import") (part "SMD-RES-5.1K-1%-1/8W(0805)"))
    )
    (comp (ref "R28")
      (value "1K")
      (footprint "eagle-import:R0805")
      (fields (field (name "MPN") "RC0805JR-071KL"))
      (libsource (lib "eagle-import") (part "SMD-RES-5.1K-1%-1/8W(0805)"))
    )
    (comp (ref "R29")
      (value "1K")
      (footprint "eagle-import:R0805")
      (fields (field (name "MPN") "RC0805JR-071KL"))
      (libsource (lib "eagle-import") (part "SMD-RES-5.1K-1%-1/8W(0805)"))
    )
    (comp (ref "R30")
      (value "1K")
      (footprint "eagle-import:R0805")
      (fields (field (name "MPN") "RC0805JR-071KL"))
      (libsource (lib "eagle-import") (part "SMD-RES-5.1K-1%-1/8W(0805)"))
    )
    (comp (ref "R55")
      (value "1K")
      (footprint "eagle-import:R0805")
      (fields (field (name "MPN") "RC0805JR-071KL"))
      (libsource (lib "eagle-import") (part "SMD-RES-5.1K-1%-1/8W(0805)"))
    )
    (comp (ref "R56")
      (value "1K")
      (footprint "eagle-import:R0805")
      (fields (field (name "MPN") "RC0805JR-071KL"))
      (libsource (lib "eagle-import") (part "SMD-RES-5.1K-1%-1/8W(0805)"))
    )
    (comp (ref "R57")
      (value "1K")
      (footprint "eagle-import:R0805")
      (fields (field (name "MPN") "RC0805JR-071KL"))
      (libsource (lib "eagle-import") (part "SMD-RES-5.1K-1%-1/8W(0805)"))
    )
    (comp (ref "R58")
      (value "1K")
      (footprint "eagle-import:R0805")
      (fields (field (name "MPN") "RC0805JR-071KL"))
      (libsource (lib "eagle-import") (part "SMD-RES-5.1K-1%-1/8W(0805)"))
    )
    (comp (ref "R59")
      (value "1K")
      (footprint "eagle-import:R0805")
      (fields (field (name "MPN") "RC0805JR-071KL"))
      (libsource (lib "eagle-import") (part "SMD-RES-5.1K-1%-1/8W(0805)"))
    )
    (comp (ref "R60")
      (value "1K")
      (footprint "eagle-import:R0805")
      (fields (field (name "MPN") "RC0805JR-071KL"))
      (libsource (lib "eagle-import") (part "SMD-RES-5.1K-1%-1/8W(0805)"))
    )
    (comp (ref "R61")
      (value "1K")
      (footprint "eagle-import:R0805")
      (fields (field (name "MPN") "RC0805JR-071KL"))
      (libsource (lib "eagle-import") (part "SMD-RES-5.1K-1%-1/8W(0805)"))
    )
    (comp (ref "R62")
      (value "1K")
      (footprint "eagle-import:R0805")
      (fields (field (name "MPN") "RC0805JR-071KL"))
      (libsource (lib "eagle-import") (part "SMD-RES-5.1K-1%-1/8W(0805)"))
    )
    (comp (ref "R63")
      (value "1K")
      (footprint "eagle-import:R0805")
      (fields (field (name "MPN") "RC0805JR-071KL"))
      (libsource (lib "eagle-import") (part "SMD-RES-5.1K-1%-1/8W(0805)"))
    )
    (comp (ref "R64")
      (value "1K")
      (footprint "eagle-import:R0805")
      (fields (field (name "MPN") "RC0805JR-071KL"))
      (libsource (lib "eagle-import") (part "SMD-RES-5.1K-1%-1/8W(0805)"))
    )
    (comp (ref "R65")
      (value "1K")
      (footprint "eagle-import:R0805")
      (fields (field (name "MPN") "RC0805JR-071KL"))
      (libsource (lib "eagle-import") (part "SMD-RES-5.1K-1%-1/8W(0805)"))
    )
    (comp (ref "R66")
      (value "1K")
      (footprint "eagle-import:R0805")
      (fields (field (name "MPN") "RC0805JR-071KL"))
      (libsource (lib "eagle-import") (part "SMD-RES-5.1K-1%-1/8W(0805)"))
    )
    (comp (ref "R67")
      (value "1K")
      (footprint "eagle-import:R0805")
      (fields (field (name "MPN") "RC0805JR-071KL"))
      (libsource (lib "eagle-import") (part "SMD-RES-5.1K-1%-1/8W(0805)"))
    )
    (comp (ref "R68")
      (value "1K")
      (footprint "eagle-import:R0805")
      (fields (field (name "MPN") "RC0805JR-071KL"))
      (libsource (lib "eagle-import") (part "SMD-RES-5.1K-1%-1/8W(0805)"))
    )
    (comp (ref "R69")
      (value "1K")
      (footprint "eagle-import:R0805")
      (fields (field (name "MPN") "RC0805JR-071KL"))
      (libsource (lib "eagle-import") (part "SMD-RES-5.1K-1%-1/8W(0805)"))
    )
    (comp (ref "R70")
      (value "1K")
      (footprint "eagle-import:R0805")
      (fields (field (name "MPN") "RC0805JR-071KL"))
      (libsource (lib "eagle-import") (part "SMD-RES-5.1K-1%-1/8W(0805)"))
    )
    (comp (ref "R79")
      (value "1K")
      (footprint "eagle-import:R0805")
      (fields (field (name "MPN") "RC0805JR-071KL"))
      (libsource (lib "eagle-import") (part "SMD-RES-5.1K-1%-1/8W(0805)"))
    )
    (comp (ref "SW1")
      (value "DIP-TOGGLE-SWITCH-2CH-(2X3P-2.54)")
      (footprint "eagle-import:SW6-2.54-9.0X3.5X3.2+2.0MM")
      (fields (field (name "MPN") "MS-22D18 G2 ROHS") (field (name "TYPE") "spdt"))
      (libsource (lib "eagle-import") (part "DIP-TOGGLE-SWITCH-2CH-(2X3P-2.54)"))
    )
    (comp (ref "U2")
      (value "SN74AC04MDREP")
      (footprint "eagle-import:SOIC127P600X175-14N")
      (fields (field (name "MOUSER_PART_NUMBER") "595-SN74AC04MDREP"))
      (libsource (lib "eagle-import") (part "SN74AC04MDREP"))
    )
    (comp (ref "U3")
      (value "SN74AC04MDREP")
      (footprint "eagle-import:SOIC127P600X175-14N")
      (fields (field (name "MOUSER_PART_NUMBER") "595-SN74AC04MDREP"))
      (libsource (lib "eagle-import") (part "SN74AC04MDREP"))
    )
    (comp (ref "U7")
      (value "NE555PSRE4")
      (footprint "eagle-import:SOIC127P780X200-8N")
      (fields (field (name "MOUSER_PART_NUMBER") "595-NE555PSRE4"))
      (libsource (lib "eagle-import") (part "NE555PSRE4"))
    )
    (comp (ref "U8")
      (value "SN74AC86DBR")
      (footprint "eagle-import:SOP65P780X200-14N")
      (fields (field (name "MOUSER_PART_NUMBER") "595-SN74AC86DBR"))
      (libsource (lib "eagle-import") (part "SN74AC86DBR"))
    )
    (comp (ref "U9")
      (value "SN74AC86DBR")
      (footprint "eagle-import:SOP65P780X200-14N")
      (fields (field (name "MOUSER_PART_NUMBER") "595-SN74AC86DBR"))
      (libsource (lib "eagle-import") (part "SN74AC86DBR"))
    )
  )
  (nets
    (net (code "1") (name "0") (class "Default")
      (node (ref "C1") (pin "1") (pinfunction "1_1") (pintype "passive"))
      (node (ref "C10") (pin "2") (pinfunction "2_2") (pintype "passive"))
      (node (ref "C11") (pin "2") (pinfunction "2_2") (pintype "passive"))
      (node (ref "C2") (pin "2") (pinfunction "2_2") (pintype "passive"))
      (node (ref "C22") (pin "1") (pinfunction "1_1") (pintype "passive"))
      (node (ref "C23") (pin "1") (pinfunction "1_1") (pintype "passive"))
      (node (ref "C26") (pin "1") (pinfunction "1_1") (pintype "passive"))
      (node (ref "C27") (pin "1") (pinfunction "1_1") (pintype "passive"))
      (node (ref "C28") (pin "2") (pinfunction "2_2") (pintype "passive"))
      (node (ref "C4") (pin "2") (pinfunction "2_2") (pintype "passive"))
      (node (ref "C5") (pin "2") (pinfunction "2_2") (pintype "passive"))
      (node (ref "C6") (pin "2") (pinfunction "2_2") (pintype "passive"))
      (node (ref "C7") (pin "2") (pinfunction "2_2") (pintype "passive"))
      (node (ref "C9") (pin "2") (pinfunction "2_2") (pintype "passive"))
      (node (ref "D2") (pin "-") (pinfunction "-_-") (pintype "passive"))
      (node (ref "G1") (pin "-") (pinfunction "-_-") (pintype "passive"))
      (node (ref "H8") (pin "1") (pinfunction "1_1") (pintype "bidirectional"))
      (node (ref "H8") (pin "10") (pinfunction "10_10") (pintype "bidirectional"))
      (node (ref "H8") (pin "11") (pinfunction "11_11") (pintype "bidirectional"))
      (node (ref "H8") (pin "12") (pinfunction "12_12") (pintype "bidirectional"))
      (node (ref "H8") (pin "13") (pinfunction "13_13") (pintype "bidirectional"))
      (node (ref "H8") (pin "14") (pinfunction "14_14") (pintype "bidirectional"))
      (node (ref "H8") (pin "15") (pinfunction "15_15") (pintype "bidirectional"))
      (node (ref "H8") (pin "16") (pinfunction "16_16") (pintype "bidirectional"))
      (node (ref "H8") (pin "17") (pinfunction "17_17") (pintype "bidirectional"))
      (node (ref "H8") (pin "18") (pinfunction "18_18") (pintype "bidirectional"))
      (node (ref "H8") (pin "2") (pinfunction "2_2") (pintype "bidirectional"))
      (node (ref "H8") (pin "3") (pinfunction "3_3") (pintype "bidirectional"))
      (node (ref "H8") (pin "4") (pinfunction "4_4") (pintype "bidirectional"))
      (node (ref "H8") (pin "5") (pinfunction "5_5") (pintype "bidirectional"))
      (node (ref "H8") (pin "6") (pinfunction "6_6") (pintype "bidirectional"))
      (node (ref "H8") (pin "7") (pinfunction "7_7") (pintype "bidirectional"))
      (node (ref "H8") (pin "8") (pinfunction "8_8") (pintype "bidirectional"))
      (node (ref "H8") (pin "9") (pinfunction "9_9") (pintype "bidirectional"))
      (node (ref "IC1") (pin "7") (pinfunction "GND_7") (pintype "bidirectional"))
      (node (ref "IC1") (pin "8") (pinfunction "SHDN_8") (pintype "bidirectional"))
      (node (ref "IC3") (pin "2") (pinfunction "GND_1_2") (pintype "bidirectional"))
      (node (ref "IC3") (pin "3") (pinfunction "GND_2_3") (pintype "bidirectional"))
      (node (ref "IC3") (pin "6") (pinfunction "GND_3_6") (pintype "bidirectional"))
      (node (ref "IC3") (pin "7") (pinfunction "GND_4_7") (pintype "bidirectional"))
      (node (ref "J1") (pin "1") (pinfunction "1_1") (pintype "bidirectional"))
      (node (ref "J1") (pin "2") (pinfunction "2_2") (pintype "bidirectional"))
      (node (ref "J1") (pin "3") (pinfunction "3_3") (pintype "bidirectional"))
      (node (ref "J1") (pin "4") (pinfunction "4_4") (pintype "bidirectional"))
      (node (ref "J1") (pin "5") (pinfunction "5_5") (pintype "bidirectional"))
      (node (ref "J1") (pin "6") (pinfunction "6_6") (pintype "bidirectional"))
      (node (ref "J2") (pin "1") (pinfunction "1_1") (pintype "bidirectional"))
      (node (ref "J2") (pin "2") (pinfunction "2_2") (pintype "bidirectional"))
      (node (ref "J2") (pin "3") (pinfunction "3_3") (pintype "bidirectional"))
      (node (ref "J2") (pin "4") (pinfunction "4_4") (pintype "bidirectional"))
      (node (ref "J2") (pin "5") (pinfunction "5_5") (pintype "bidirectional"))
      (node (ref "J2") (pin "6") (pinfunction "6_6") (pintype "bidirectional"))
      (node (ref "J3") (pin "1") (pinfunction "1_1") (pintype "bidirectional"))
      (node (ref "J3") (pin "2") (pinfunction "2_2") (pintype "bidirectional"))
      (node (ref "J3") (pin "3") (pinfunction "3_3") (pintype "bidirectional"))
      (node (ref "J3") (pin "4") (pinfunction "4_4") (pintype "bidirectional"))
      (node (ref "J3") (pin "5") (pinfunction "5_5") (pintype "bidirectional"))
      (node (ref "J3") (pin "6") (pinfunction "6_6") (pintype "bidirectional"))
      (node (ref "J3") (pin "7") (pinfunction "7_7") (pintype "bidirectional"))
      (node (ref "J3") (pin "8") (pinfunction "8_8") (pintype "bidirectional"))
      (node (ref "J4") (pin "1") (pinfunction "1_1") (pintype "bidirectional"))
      (node (ref "J4") (pin "2") (pinfunction "2_2") (pintype "bidirectional"))
      (node (ref "J4") (pin "3") (pinfunction "3_3") (pintype "bidirectional"))
      (node (ref "J4") (pin "4") (pinfunction "4_4") (pintype "bidirectional"))
      (node (ref "J4") (pin "5") (pinfunction "5_5") (pintype "bidirectional"))
      (node (ref "J4") (pin "6") (pinfunction "6_6") (pintype "bidirectional"))
      (node (ref "J4") (pin "7") (pinfunction "7_7") (pintype "bidirectional"))
      (node (ref "J4") (pin "8") (pinfunction "8_8") (pintype "bidirectional"))
      (node (ref "J5") (pin "1") (pinfunction "1_1") (pintype "bidirectional"))
      (node (ref "J5") (pin "2") (pinfunction "2_2") (pintype "bidirectional"))
      (node (ref "J5") (pin "3") (pinfunction "3_3") (pintype "bidirectional"))
      (node (ref "J5") (pin "4") (pinfunction "4_4") (pintype "bidirectional"))
      (node (ref "J5") (pin "5") (pinfunction "5_5") (pintype "bidirectional"))
      (node (ref "J5") (pin "6") (pinfunction "6_6") (pintype "bidirectional"))
      (node (ref "J5") (pin "7") (pinfunction "7_7") (pintype "bidirectional"))
      (node (ref "J5") (pin "8") (pinfunction "8_8") (pintype "bidirectional"))
      (node (ref "J6") (pin "1") (pinfunction "1_1") (pintype "bidirectional"))
      (node (ref "J6") (pin "2") (pinfunction "2_2") (pintype "bidirectional"))
      (node (ref "J6") (pin "3") (pinfunction "3_3") (pintype "bidirectional"))
      (node (ref "J6") (pin "4") (pinfunction "4_4") (pintype "bidirectional"))
      (node (ref "J6") (pin "5") (pinfunction "5_5") (pintype "bidirectional"))
      (node (ref "J6") (pin "6") (pinfunction "6_6") (pintype "bidirectional"))
      (node (ref "J6") (pin "7") (pinfunction "7_7") (pintype "bidirectional"))
      (node (ref "J6") (pin "8") (pinfunction "8_8") (pintype "bidirectional"))
      (node (ref "J7") (pin "1") (pinfunction "1_1") (pintype "bidirectional"))
      (node (ref "J7") (pin "2") (pinfunction "2_2") (pintype "bidirectional"))
      (node (ref "J7") (pin "3") (pinfunction "3_3") (pintype "bidirectional"))
      (node (ref "J7") (pin "4") (pinfunction "4_4") (pintype "bidirectional"))
      (node (ref "J7") (pin "5") (pinfunction "5_5") (pintype "bidirectional"))
      (node (ref "J7") (pin "6") (pinfunction "6_6") (pintype "bidirectional"))
      (node (ref "J7") (pin "7") (pinfunction "7_7") (pintype "bidirectional"))
      (node (ref "J7") (pin "8") (pinfunction "8_8") (pintype "bidirectional"))
      (node (ref "J8") (pin "1") (pinfunction "1_1") (pintype "bidirectional"))
      (node (ref "J8") (pin "2") (pinfunction "2_2") (pintype "bidirectional"))
      (node (ref "J8") (pin "3") (pinfunction "3_3") (pintype "bidirectional"))
      (node (ref "J8") (pin "4") (pinfunction "4_4") (pintype "bidirectional"))
      (node (ref "J8") (pin "5") (pinfunction "5_5") (pintype "bidirectional"))
      (node (ref "J8") (pin "6") (pinfunction "6_6") (pintype "bidirectional"))
      (node (ref "J8") (pin "7") (pinfunction "7_7") (pintype "bidirectional"))
      (node (ref "J8") (pin "8") (pinfunction "8_8") (pintype "bidirectional"))
      (node (ref "Q1") (pin "1") (pinfunction "E_1") (pintype "bidirectional"))
      (node (ref "R72") (pin "2") (pinfunction "2_2") (pintype "passive"))
      (node (ref "U1") (pin "7") (pinfunction "GND_7") (pintype "bidirectional"))
      (node (ref "U2") (pin "7") (pinfunction "GND_7") (pintype "bidirectional"))
      (node (ref "U3") (pin "7") (pinfunction "GND_7") (pintype "bidirectional"))
      (node (ref "U4") (pin "7") (pinfunction "GND_7") (pintype "bidirectional"))
      (node (ref "U5") (pin "7") (pinfunction "GND_7") (pintype "bidirectional"))
      (node (ref "U6") (pin "7") (pinfunction "GND_7") (pintype "bidirectional"))
      (node (ref "U7") (pin "1") (pinfunction "GND_1") (pintype "power_in"))
      (node (ref "U8") (pin "7") (pinfunction "GND_7") (pintype "bidirectional"))
      (node (ref "U9") (pin "7") (pinfunction "GND_7") (pintype "bidirectional"))
      (node (ref "USB") (pin "MH1") (pinfunction "MH1_MH1") (pintype "bidirectional"))
      (node (ref "USB") (pin "MH2") (pinfunction "MH2_MH2") (pintype "bidirectional"))
      (node (ref "USB") (pin "MP1") (pinfunction "MP1_MP1") (pintype "bidirectional"))
      (node (ref "USB") (pin "MP2") (pinfunction "MP2_MP2") (pintype "bidirectional"))
      (node (ref "USB") (pin "MP3") (pinfunction "MP3_MP3") (pintype "bidirectional"))
      (node (ref "USB") (pin "MP4") (pinfunction "MP4_MP4") (pintype "bidirectional"))
    )
    (net (code "2") (name "C1A") (class "Default")
      (node (ref "C1N") (pin "1") (pinfunction "+_1") (pintype "bidirectional"))
      (node (ref "H6") (pin "31") (pinfunction "31_31") (pintype "bidirectional"))
    )
    (net (code "3") (name "C1B") (class "Default")
      (node (ref "C1N") (pin "2") (pinfunction "-_2") (pintype "bidirectional"))
      (node (ref "H6") (pin "32") (pinfunction "32_32") (pintype "bidirectional"))
    )
    (net (code "4") (name "C2A") (class "Default")
      (node (ref "C2N") (pin "1") (pinfunction "+_1") (pintype "bidirectional"))
      (node (ref "H6") (pin "29") (pinfunction "29_29") (pintype "bidirectional"))
    )
    (net (code "5") (name "C2B") (class "Default")
      (node (ref "C2N") (pin "2") (pinfunction "-_2") (pintype "bidirectional"))
      (node (ref "H6") (pin "30") (pinfunction "30_30") (pintype "bidirectional"))
    )
    (net (code "6") (name "C3A") (class "Default")
      (node (ref "C3N") (pin "1") (pinfunction "+_1") (pintype "bidirectional"))
      (node (ref "H6") (pin "27") (pinfunction "27_27") (pintype "bidirectional"))
    )
    (net (code "7") (name "C3B") (class "Default")
      (node (ref "C3N") (pin "2") (pinfunction "-_2") (pintype "bidirectional"))
      (node (ref "H6") (pin "28") (pinfunction "28_28") (pintype "bidirectional"))
    )
    (net (code "8") (name "C4A") (class "Default")
      (node (ref "C4N") (pin "1") (pinfunction "+_1") (pintype "bidirectional"))
      (node (ref "H6") (pin "25") (pinfunction "25_25") (pintype "bidirectional"))
    )
    (net (code "9") (name "C4B") (class "Default")
      (node (ref "C4N") (pin "2") (pinfunction "-_2") (pintype "bidirectional"))
      (node (ref "H6") (pin "26") (pinfunction "26_26") (pintype "bidirectional"))
    )
    (net (code "10") (name "C5A") (class "Default")
      (node (ref "C5N") (pin "1") (pinfunction "+_1") (pintype "bidirectional"))
      (node (ref "H6") (pin "23") (pinfunction "23_23") (pintype "bidirectional"))
    )
    (net (code "11") (name "C5B") (class "Default")
      (node (ref "C5N") (pin "2") (pinfunction "-_2") (pintype "bidirectional"))
      (node (ref "H6") (pin "24") (pinfunction "24_24") (pintype "bidirectional"))
    )
    (net (code "12") (name "C6A") (class "Default")
      (node (ref "C6N") (pin "1") (pinfunction "+_1") (pintype "bidirectional"))
      (node (ref "H6") (pin "21") (pinfunction "21_21") (pintype "bidirectional"))
    )
    (net (code "13") (name "C6B") (class "Default")
      (node (ref "C6N") (pin "2") (pinfunction "-_2") (pintype "bidirectional"))
      (node (ref "H6") (pin "22") (pinfunction "22_22") (pintype "bidirectional"))
    )
    (net (code "14") (name "C7A") (class "Default")
      (node (ref "C7N") (pin "1") (pinfunction "+_1") (pintype "bidirectional"))
      (node (ref "H6") (pin "19") (pinfunction "19_19") (pintype "bidirectional"))
    )
    (net (code "15") (name "C7B") (class "Default")
      (node (ref "C7N") (pin "2") (pinfunction "-_2") (pintype "bidirectional"))
      (node (ref "H6") (pin "20") (pinfunction "20_20") (pintype "bidirectional"))
    )
    (net (code "16") (name "C8A") (class "Default")
      (node (ref "C8N") (pin "1") (pinfunction "+_1") (pintype "bidirectional"))
      (node (ref "H6") (pin "17") (pinfunction "17_17") (pintype "bidirectional"))
    )
    (net (code "17") (name "C8B") (class "Default")
      (node (ref "C8N") (pin "2") (pinfunction "-_2") (pintype "bidirectional"))
      (node (ref "H6") (pin "18") (pinfunction "18_18") (pintype "bidirectional"))
    )
    (net (code "18") (name "C9A") (class "Default")
      (node (ref "C9N") (pin "1") (pinfunction "+_1") (pintype "bidirectional"))
      (node (ref "H6") (pin "15") (pinfunction "15_15") (pintype "bidirectional"))
    )
    (net (code "19") (name "C9B") (class "Default")
      (node (ref "C9N") (pin "2") (pinfunction "-_2") (pintype "bidirectional"))
      (node (ref "H6") (pin "16") (pinfunction "16_16") (pintype "bidirectional"))
    )
    (net (code "20") (name "C10A") (class "Default")
      (node (ref "C10N") (pin "1") (pinfunction "+_1") (pintype "bidirectional"))
      (node (ref "H6") (pin "13") (pinfunction "13_13") (pintype "bidirectional"))
    )
    (net (code "21") (name "C10B") (class "Default")
      (node (ref "C10N") (pin "2") (pinfunction "-_2") (pintype "bidirectional"))
      (node (ref "H6") (pin "14") (pinfunction "14_14") (pintype "bidirectional"))
    )
    (net (code "22") (name "C11A") (class "Default")
      (node (ref "C11N") (pin "1") (pinfunction "+_1") (pintype "bidirectional"))
      (node (ref "H6") (pin "11") (pinfunction "11_11") (pintype "bidirectional"))
    )
    (net (code "23") (name "C11B") (class "Default")
      (node (ref "C11N") (pin "2") (pinfunction "-_2") (pintype "bidirectional"))
      (node (ref "H6") (pin "12") (pinfunction "12_12") (pintype "bidirectional"))
    )
    (net (code "24") (name "C12A") (class "Default")
      (node (ref "C12N") (pin "1") (pinfunction "+_1") (pintype "bidirectional"))
      (node (ref "H6") (pin "9") (pinfunction "9_9") (pintype "bidirectional"))
    )
    (net (code "25") (name "C12B") (class "Default")
      (node (ref "C12N") (pin "2") (pinfunction "-_2") (pintype "bidirectional"))
      (node (ref "H6") (pin "10") (pinfunction "10_10") (pintype "bidirectional"))
    )
    (net (code "26") (name "LED1A") (class "Default")
      (node (ref "H7") (pin "13") (pinfunction "13_13") (pintype "bidirectional"))
      (node (ref "L1") (pin "2") (pinfunction "K_2") (pintype "bidirectional"))
    )
    (net (code "27") (name "LED1B") (class "Default")
      (node (ref "H7") (pin "14") (pinfunction "14_14") (pintype "bidirectional"))
      (node (ref "L1") (pin "1") (pinfunction "A_1") (pintype "bidirectional"))
    )
    (net (code "28") (name "LED2A") (class "Default")
      (node (ref "H7") (pin "11") (pinfunction "11_11") (pintype "bidirectional"))
      (node (ref "L2") (pin "2") (pinfunction "K_2") (pintype "bidirectional"))
    )
    (net (code "29") (name "LED2B") (class "Default")
      (node (ref "H7") (pin "12") (pinfunction "12_12") (pintype "bidirectional"))
      (node (ref "L2") (pin "1") (pinfunction "A_1") (pintype "bidirectional"))
    )
    (net (code "30") (name "LED3A") (class "Default")
      (node (ref "H7") (pin "9") (pinfunction "9_9") (pintype "bidirectional"))
      (node (ref "L3") (pin "2") (pinfunction "K_2") (pintype "bidirectional"))
    )
    (net (code "31") (name "LED3B") (class "Default")
      (node (ref "H7") (pin "10") (pinfunction "10_10") (pintype "bidirectional"))
      (node (ref "L3") (pin "1") (pinfunction "A_1") (pintype "bidirectional"))
    )
    (net (code "32") (name "LED4A") (class "Default")
      (node (ref "H7") (pin "7") (pinfunction "7_7") (pintype "bidirectional"))
      (node (ref "L4") (pin "2") (pinfunction "K_2") (pintype "bidirectional"))
    )
    (net (code "33") (name "LED4B") (class "Default")
      (node (ref "H7") (pin "8") (pinfunction "8_8") (pintype "bidirectional"))
      (node (ref "L4") (pin "1") (pinfunction "A_1") (pintype "bidirectional"))
    )
    (net (code "34") (name "LED5A") (class "Default")
      (node (ref "H7") (pin "5") (pinfunction "5_5") (pintype "bidirectional"))
      (node (ref "L5") (pin "2") (pinfunction "K_2") (pintype "bidirectional"))
    )
    (net (code "35") (name "LED5B") (class "Default")
      (node (ref "H7") (pin "6") (pinfunction "6_6") (pintype "bidirectional"))
      (node (ref "L5") (pin "1") (pinfunction "A_1") (pintype "bidirectional"))
    )
    (net (code "36") (name "LED6A") (class "Default")
      (node (ref "H7") (pin "3") (pinfunction "3_3") (pintype "bidirectional"))
      (node (ref "L6") (pin "1") (pinfunction "K_1") (pintype "bidirectional"))
    )
    (net (code "37") (name "LED6B") (class "Default")
      (node (ref "H7") (pin "4") (pinfunction "4_4") (pintype "bidirectional"))
      (node (ref "L6") (pin "2") (pinfunction "A_2") (pintype "bidirectional"))
    )
    (net (code "38") (name "Net-(D2-Pad+)") (class "Default")
      (node (ref "D2") (pin "+") (pinfunction "+_+") (pintype "passive"))
      (node (ref "R71") (pin "2") (pinfunction "2_2") (pintype "passive"))
    )
    (net (code "39") (name "Net-(IC1-C1+)") (class "Default")
      (node (ref "C24") (pin "2") (pinfunction "2_2") (pintype "passive"))
      (node (ref "IC1") (pin "2") (pinfunction "C1+_2") (pintype "bidirectional"))
    )
    (net (code "40") (name "Net-(IC1-C1-)") (class "Default")
      (node (ref "C24") (pin "1") (pinfunction "1_1") (pintype "passive"))
      (node (ref "IC1") (pin "1") (pinfunction "C1-_1") (pintype "bidirectional"))
    )
    (net (code "41") (name "Net-(IC1-C2+)") (class "Default")
      (node (ref "C25") (pin "2") (pinfunction "2_2") (pintype "passive"))
      (node (ref "IC1") (pin "4") (pinfunction "C2+_4") (pintype "bidirectional"))
    )
    (net (code "42") (name "Net-(IC1-C2-)") (class "Default")
      (node (ref "C25") (pin "1") (pinfunction "1_1") (pintype "passive"))
      (node (ref "IC1") (pin "3") (pinfunction "C2-_3") (pintype "bidirectional"))
    )
    (net (code "43") (name "Net-(IC3-IN)") (class "Default")
      (node (ref "C26") (pin "2") (pinfunction "2_2") (pintype "passive"))
      (node (ref "G1") (pin "+") (pinfunction "+_+") (pintype "passive"))
      (node (ref "IC3") (pin "8") (pinfunction "IN_8") (pintype "bidirectional"))
    )
    (net (code "44") (name "Net-(IC3-SD)") (class "Default")
      (node (ref "IC3") (pin "5") (pinfunction "SD_5") (pintype "bidirectional"))
      (node (ref "R72") (pin "1") (pinfunction "1_1") (pintype "passive"))
      (node (ref "USB") (pin "1") (pinfunction "1_1") (pintype "bidirectional"))
    )
    (net (code "45") (name "Net-(Q1-B)") (class "Default")
      (node (ref "Q1") (pin "2") (pinfunction "B_2") (pintype "bidirectional"))
      (node (ref "R73") (pin "2") (pinfunction "2_2") (pintype "passive"))
    )
    (net (code "46") (name "Net-(Q1-C)") (class "Default")
      (node (ref "LS1") (pin "2") (pinfunction "2_2") (pintype "bidirectional"))
      (node (ref "Q1") (pin "3") (pinfunction "C_3") (pintype "bidirectional"))
      (node (ref "R74") (pin "1") (pinfunction "1_1") (pintype "passive"))
    )
    (net (code "47") (name "Net-(U7-CONT)") (class "Default")
      (node (ref "C1") (pin "2") (pinfunction "2_2") (pintype "passive"))
      (node (ref "U7") (pin "5") (pinfunction "CONT_5") (pintype "bidirectional"))
    )
    (net (code "48") (name "Net-(U7-RESET)") (class "Default")
      (node (ref "H2") (pin "3") (pinfunction "3_3") (pintype "bidirectional"))
      (node (ref "R79") (pin "2") (pinfunction "2_2") (pintype "passive"))
      (node (ref "U7") (pin "4") (pinfunction "RESET_4") (pintype "bidirectional"))
    )
    (net (code "49") (name "P12-0V") (class "Default")
      (node (ref "C23") (pin "2") (pinfunction "2_2") (pintype "passive"))
      (node (ref "H8") (pin "19") (pinfunction "19_19") (pintype "bidirectional"))
      (node (ref "H8") (pin "21") (pinfunction "21_21") (pintype "bidirectional"))
      (node (ref "H8") (pin "23") (pinfunction "23_23") (pintype "bidirectional"))
      (node (ref "H8") (pin "25") (pinfunction "25_25") (pintype "bidirectional"))
      (node (ref "H8") (pin "27") (pinfunction "27_27") (pintype "bidirectional"))
      (node (ref "H8") (pin "29") (pinfunction "29_29") (pintype "bidirectional"))
      (node (ref "H8") (pin "31") (pinfunction "31_31") (pintype "bidirectional"))
      (node (ref "IC1") (pin "6") (pinfunction "VOUT_6") (pintype "bidirectional"))
    )
    (net (code "50") (name "PRA") (class "Default")
      (node (ref "H7") (pin "15") (pinfunction "15_15") (pintype "bidirectional"))
      (node (ref "PR1") (pin "1") (pinfunction "P$1_1") (pintype "bidirectional"))
    )
    (net (code "51") (name "PRB") (class "Default")
      (node (ref "H7") (pin "16") (pinfunction "16_16") (pintype "bidirectional"))
      (node (ref "PR1") (pin "2") (pinfunction "P$2_2") (pintype "bidirectional"))
    )
    (net (code "52") (name "R1A") (class "Default")
      (node (ref "H6") (pin "7") (pinfunction "7_7") (pintype "bidirectional"))
      (node (ref "R1") (pin "1") (pinfunction "1_1") (pintype "bidirectional"))
    )
    (net (code "53") (name "R1B") (class "Default")
      (node (ref "H6") (pin "8") (pinfunction "8_8") (pintype "bidirectional"))
      (node (ref "R1") (pin "2") (pinfunction "2_2") (pintype "bidirectional"))
    )
    (net (code "54") (name "R2A") (class "Default")
      (node (ref "H6") (pin "5") (pinfunction "5_5") (pintype "bidirectional"))
      (node (ref "R2") (pin "1") (pinfunction "1_1") (pintype "bidirectional"))
    )
    (net (code "55") (name "R2B") (class "Default")
      (node (ref "H6") (pin "6") (pinfunction "6_6") (pintype "bidirectional"))
      (node (ref "R2") (pin "2") (pinfunction "2_2") (pintype "bidirectional"))
    )
    (net (code "56") (name "R3A") (class "Default")
      (node (ref "H6") (pin "3") (pinfunction "3_3") (pintype "bidirectional"))
      (node (ref "R3") (pin "1") (pinfunction "1_1") (pintype "bidirectional"))
    )
    (net (code "57") (name "R3B") (class "Default")
      (node (ref "H6") (pin "4") (pinfunction "4_4") (pintype "bidirectional"))
      (node (ref "R3") (pin "2") (pinfunction "2_2") (pintype "bidirectional"))
    )
    (net (code "58") (name "R4A") (class "Default")
      (node (ref "H6") (pin "1") (pinfunction "1_1") (pintype "bidirectional"))
      (node (ref "R4") (pin "1") (pinfunction "1_1") (pintype "bidirectional"))
    )
    (net (code "59") (name "R4B") (class "Default")
      (node (ref "H6") (pin "2") (pinfunction "2_2") (pintype "bidirectional"))
      (node (ref "R4") (pin "2") (pinfunction "2_2") (pintype "bidirectional"))
    )
    (net (code "60") (name "R5A") (class "Default")
      (node (ref "H5") (pin "11") (pinfunction "11_11") (pintype "bidirectional"))
      (node (ref "R5") (pin "1") (pinfunction "1_1") (pintype "bidirectional"))
    )
    (net (code "61") (name "R5B") (class "Default")
      (node (ref "H5") (pin "12") (pinfunction "12_12") (pintype "bidirectional"))
      (node (ref "R5") (pin "2") (pinfunction "2_2") (pintype "bidirectional"))
    )
    (net (code "62") (name "R6A") (class "Default")
      (node (ref "H5") (pin "9") (pinfunction "9_9") (pintype "bidirectional"))
      (node (ref "R6") (pin "1") (pinfunction "1_1") (pintype "bidirectional"))
    )
    (net (code "63") (name "R6B") (class "Default")
      (node (ref "H5") (pin "10") (pinfunction "10_10") (pintype "bidirectional"))
      (node (ref "R6") (pin "2") (pinfunction "2_2") (pintype "bidirectional"))
    )
    (net (code "64") (name "R7A") (class "Default")
      (node (ref "H5") (pin "7") (pinfunction "7_7") (pintype "bidirectional"))
      (node (ref "R7") (pin "1") (pinfunction "1_1") (pintype "passive"))
    )
    (net (code "65") (name "R7B") (class "Default")
      (node (ref "H5") (pin "8") (pinfunction "8_8") (pintype "bidirectional"))
      (node (ref "R7") (pin "2") (pinfunction "2_2") (pintype "passive"))
    )
    (net (code "66") (name "R8A") (class "Default")
      (node (ref "H5") (pin "5") (pinfunction "5_5") (pintype "bidirectional"))
      (node (ref "R8") (pin "1") (pinfunction "1_1") (pintype "passive"))
    )
    (net (code "67") (name "R8B") (class "Default")
      (node (ref "H5") (pin "6") (pinfunction "6_6") (pintype "bidirectional"))
      (node (ref "R8") (pin "2") (pinfunction "2_2") (pintype "passive"))
    )
    (net (code "68") (name "R9A") (class "Default")
      (node (ref "H5") (pin "3") (pinfunction "3_3") (pintype "bidirectional"))
      (node (ref "R9") (pin "1") (pinfunction "1_1") (pintype "passive"))
    )
    (net (code "69") (name "R9B") (class "Default")
      (node (ref "H5") (pin "4") (pinfunction "4_4") (pintype "bidirectional"))
      (node (ref "R9") (pin "2") (pinfunction "2_2") (pintype "passive"))
    )
    (net (code "70") (name "R10A") (class "Default")
      (node (ref "H5") (pin "1") (pinfunction "1_1") (pintype "bidirectional"))
      (node (ref "R10") (pin "1") (pinfunction "1_1") (pintype "passive"))
    )
    (net (code "71") (name "R10B") (class "Default")
      (node (ref "H5") (pin "2") (pinfunction "2_2") (pintype "bidirectional"))
      (node (ref "R10") (pin "2") (pinfunction "2_2") (pintype "passive"))
    )
    (net (code "72") (name "R11A") (class "Default")
      (node (ref "H7") (pin "31") (pinfunction "31_31") (pintype "bidirectional"))
      (node (ref "R11") (pin "1") (pinfunction "1_1") (pintype "passive"))
    )
    (net (code "73") (name "R11B") (class "Default")
      (node (ref "H7") (pin "32") (pinfunction "32_32") (pintype "bidirectional"))
      (node (ref "R11") (pin "2") (pinfunction "2_2") (pintype "passive"))
    )
    (net (code "74") (name "R12A") (class "Default")
      (node (ref "H7") (pin "29") (pinfunction "29_29") (pintype "bidirectional"))
      (node (ref "R12") (pin "1") (pinfunction "1_1") (pintype "passive"))
    )
    (net (code "75") (name "R12B") (class "Default")
      (node (ref "H7") (pin "30") (pinfunction "30_30") (pintype "bidirectional"))
      (node (ref "R12") (pin "2") (pinfunction "2_2") (pintype "passive"))
    )
    (net (code "76") (name "R13A") (class "Default")
      (node (ref "H7") (pin "27") (pinfunction "27_27") (pintype "bidirectional"))
      (node (ref "R13") (pin "1") (pinfunction "1_1") (pintype "passive"))
    )
    (net (code "77") (name "R13B") (class "Default")
      (node (ref "H7") (pin "28") (pinfunction "28_28") (pintype "bidirectional"))
      (node (ref "R13") (pin "2") (pinfunction "2_2") (pintype "passive"))
    )
    (net (code "78") (name "R14A") (class "Default")
      (node (ref "H7") (pin "25") (pinfunction "25_25") (pintype "bidirectional"))
      (node (ref "R14") (pin "1") (pinfunction "1_1") (pintype "passive"))
    )
    (net (code "79") (name "R14B") (class "Default")
      (node (ref "H7") (pin "26") (pinfunction "26_26") (pintype "bidirectional"))
      (node (ref "R14") (pin "2") (pinfunction "2_2") (pintype "passive"))
    )
    (net (code "80") (name "R15A") (class "Default")
      (node (ref "H7") (pin "23") (pinfunction "23_23") (pintype "bidirectional"))
      (node (ref "R15") (pin "1") (pinfunction "1_1") (pintype "passive"))
    )
    (net (code "81") (name "R15B") (class "Default")
      (node (ref "H7") (pin "24") (pinfunction "24_24") (pintype "bidirectional"))
      (node (ref "R15") (pin "2") (pinfunction "2_2") (pintype "passive"))
    )
    (net (code "82") (name "R16A") (class "Default")
      (node (ref "H7") (pin "21") (pinfunction "21_21") (pintype "bidirectional"))
      (node (ref "R16") (pin "1") (pinfunction "1_1") (pintype "passive"))
    )
    (net (code "83") (name "R16B") (class "Default")
      (node (ref "H7") (pin "22") (pinfunction "22_22") (pintype "bidirectional"))
      (node (ref "R16") (pin "2") (pinfunction "2_2") (pintype "passive"))
    )
    (net (code "84") (name "R17A") (class "Default")
      (node (ref "H7") (pin "19") (pinfunction "19_19") (pintype "bidirectional"))
      (node (ref "R17") (pin "1") (pinfunction "1_1") (pintype "passive"))
    )
    (net (code "85") (name "R17B") (class "Default")
      (node (ref "H7") (pin "20") (pinfunction "20_20") (pintype "bidirectional"))
      (node (ref "R17") (pin "2") (pinfunction "2_2") (pintype "passive"))
    )
    (net (code "86") (name "R18A") (class "Default")
      (node (ref "H7") (pin "17") (pinfunction "17_17") (pintype "bidirectional"))
      (node (ref "R18") (pin "1") (pinfunction "1_1") (pintype "passive"))
    )
    (net (code "87") (name "R18B") (class "Default")
      (node (ref "H7") (pin "18") (pinfunction "18_18") (pintype "bidirectional"))
      (node (ref "R18") (pin "2") (pinfunction "2_2") (pintype "passive"))
    )
    (net (code "88") (name "S1") (class "Default")
      (node (ref "H3") (pin "7") (pinfunction "7_7") (pintype "bidirectional"))
      (node (ref "K1") (pin "1") (pinfunction "A0_1") (pintype "bidirectional"))
      (node (ref "K1") (pin "4") (pinfunction "A1_4") (pintype "bidirectional"))
    )
    (net (code "89") (name "S2") (class "Default")
      (node (ref "H3") (pin "5") (pinfunction "5_5") (pintype "bidirectional"))
      (node (ref "K1") (pin "2") (pinfunction "B0_2") (pintype "bidirectional"))
      (node (ref "K1") (pin "3") (pinfunction "B1_3") (pintype "bidirectional"))
    )
    (net (code "90") (name "S5") (class "Default")
      (node (ref "H3") (pin "3") (pinfunction "3_3") (pintype "bidirectional"))
      (node (ref "K2") (pin "1") (pinfunction "A0_1") (pintype "bidirectional"))
      (node (ref "K2") (pin "4") (pinfunction "A1_4") (pintype "bidirectional"))
    )
    (net (code "91") (name "S7") (class "Default")
      (node (ref "H3") (pin "1") (pinfunction "1_1") (pintype "bidirectional"))
      (node (ref "K2") (pin "2") (pinfunction "B0_2") (pintype "bidirectional"))
      (node (ref "K2") (pin "3") (pinfunction "B1_3") (pintype "bidirectional"))
    )
    (net (code "92") (name "S9") (class "Default")
      (node (ref "B14") (pin "1") (pinfunction "NO_1_1") (pintype "bidirectional"))
      (node (ref "B14") (pin "2") (pinfunction "NO_2_2") (pintype "bidirectional"))
      (node (ref "H4") (pin "1") (pinfunction "1_1") (pintype "bidirectional"))
    )
    (net (code "93") (name "S10") (class "Default")
      (node (ref "B14") (pin "3") (pinfunction "COM_1_3") (pintype "bidirectional"))
      (node (ref "B14") (pin "4") (pinfunction "COM_2_4") (pintype "bidirectional"))
      (node (ref "H4") (pin "2") (pinfunction "2_2") (pintype "bidirectional"))
    )
    (net (code "94") (name "S11") (class "Default")
      (node (ref "B7") (pin "1") (pinfunction "NO_1_1") (pintype "bidirectional"))
      (node (ref "B7") (pin "2") (pinfunction "NO_2_2") (pintype "bidirectional"))
      (node (ref "H5") (pin "31") (pinfunction "31_31") (pintype "bidirectional"))
    )
    (net (code "95") (name "S12") (class "Default")
      (node (ref "B7") (pin "3") (pinfunction "COM_1_3") (pintype "bidirectional"))
      (node (ref "B7") (pin "4") (pinfunction "COM_2_4") (pintype "bidirectional"))
      (node (ref "H5") (pin "32") (pinfunction "32_32") (pintype "bidirectional"))
    )
    (net (code "96") (name "S13") (class "Default")
      (node (ref "B8") (pin "1") (pinfunction "NO_1_1") (pintype "bidirectional"))
      (node (ref "B8") (pin "2") (pinfunction "NO_2_2") (pintype "bidirectional"))
      (node (ref "H5") (pin "29") (pinfunction "29_29") (pintype "bidirectional"))
    )
    (net (code "97") (name "S14") (class "Default")
      (node (ref "B8") (pin "3") (pinfunction "COM_1_3") (pintype "bidirectional"))
      (node (ref "B8") (pin "4") (pinfunction "COM_2_4") (pintype "bidirectional"))
      (node (ref "H5") (pin "30") (pinfunction "30_30") (pintype "bidirectional"))
    )
    (net (code "98") (name "S15") (class "Default")
      (node (ref "B9") (pin "1") (pinfunction "NO_1_1") (pintype "bidirectional"))
      (node (ref "B9") (pin "2") (pinfunction "NO_2_2") (pintype "bidirectional"))
      (node (ref "H5") (pin "27") (pinfunction "27_27") (pintype "bidirectional"))
    )
    (net (code "99") (name "S16") (class "Default")
      (node (ref "B9") (pin "3") (pinfunction "COM_1_3") (pintype "bidirectional"))
      (node (ref "B9") (pin "4") (pinfunction "COM_2_4") (pintype "bidirectional"))
      (node (ref "H5") (pin "28") (pinfunction "28_28") (pintype "bidirectional"))
    )
    (net (code "100") (name "S17") (class "Default")
      (node (ref "B10") (pin "1") (pinfunction "NO_1_1") (pintype "bidirectional"))
      (node (ref "B10") (pin "2") (pinfunction "NO_2_2") (pintype "bidirectional"))
      (node (ref "H5") (pin "25") (pinfunction "25_25") (pintype "bidirectional"))
    )
    (net (code "101") (name "S18") (class "Default")
      (node (ref "B10") (pin "3") (pinfunction "COM_1_3") (pintype "bidirectional"))
      (node (ref "B10") (pin "4") (pinfunction "COM_2_4") (pintype "bidirectional"))
      (node (ref "H5") (pin "26") (pinfunction "26_26") (pintype "bidirectional"))
    )
    (net (code "102") (name "S19") (class "Default")
      (node (ref "B11") (pin "1") (pinfunction "NO_1_1") (pintype "bidirectional"))
      (node (ref "B11") (pin "2") (pinfunction "NO_2_2") (pintype "bidirectional"))
      (node (ref "H5") (pin "23") (pinfunction "23_23") (pintype "bidirectional"))
    )
    (net (code "103") (name "S20") (class "Default")
      (node (ref "B11") (pin "3") (pinfunction "COM_1_3") (pintype "bidirectional"))
      (node (ref "B11") (pin "4") (pinfunction "COM_2_4") (pintype "bidirectional"))
      (node (ref "H5") (pin "24") (pinfunction "24_24") (pintype "bidirectional"))
    )
    (net (code "104") (name "S21") (class "Default")
      (node (ref "B12") (pin "1") (pinfunction "NO_1_1") (pintype "bidirectional"))
      (node (ref "B12") (pin "2") (pinfunction "NO_2_2") (pintype "bidirectional"))
      (node (ref "H5") (pin "21") (pinfunction "21_21") (pintype "bidirectional"))
    )
    (net (code "105") (name "S22") (class "Default")
      (node (ref "B12") (pin "3") (pinfunction "COM_1_3") (pintype "bidirectional"))
      (node (ref "B12") (pin "4") (pinfunction "COM_2_4") (pintype "bidirectional"))
      (node (ref "H5") (pin "22") (pinfunction "22_22") (pintype "bidirectional"))
    )
    (net (code "106") (name "S23") (class "Default")
      (node (ref "B13") (pin "1") (pinfunction "NO_1_1") (pintype "bidirectional"))
      (node (ref "B13") (pin "2") (pinfunction "NO_2_2") (pintype "bidirectional"))
      (node (ref "H5") (pin "19") (pinfunction "19_19") (pintype "bidirectional"))
    )
    (net (code "107") (name "S24") (class "Default")
      (node (ref "B13") (pin "3") (pinfunction "COM_1_3") (pintype "bidirectional"))
      (node (ref "B13") (pin "4") (pinfunction "COM_2_4") (pintype "bidirectional"))
      (node (ref "H5") (pin "20") (pinfunction "20_20") (pintype "bidirectional"))
    )
    (net (code "108") (name "S26") (class "Default")
      (node (ref "H4") (pin "7") (pinfunction "7_7") (pintype "bidirectional"))
      (node (ref "H4") (pin "8") (pinfunction "8_8") (pintype "bidirectional"))
      (node (ref "SW1") (pin "CH1A") (pinfunction "CH1A_CH1A") (pintype "bidirectional"))
      (node (ref "SW1") (pin "CH2A") (pinfunction "CH2A_CH2A") (pintype "bidirectional"))
    )
    (net (code "109") (name "S27") (class "Default")
      (node (ref "H4") (pin "5") (pinfunction "5_5") (pintype "bidirectional"))
      (node (ref "H4") (pin "6") (pinfunction "6_6") (pintype "bidirectional"))
      (node (ref "SW1") (pin "COM1") (pinfunction "COM1_COM1") (pintype "bidirectional"))
      (node (ref "SW1") (pin "COM2") (pinfunction "COM2_COM2") (pintype "bidirectional"))
    )
    (net (code "110") (name "S29") (class "Default")
      (node (ref "H4") (pin "3") (pinfunction "3_3") (pintype "bidirectional"))
      (node (ref "H4") (pin "4") (pinfunction "4_4") (pintype "bidirectional"))
      (node (ref "SW1") (pin "CH1B") (pinfunction "CH1B_CH1B") (pintype "bidirectional"))
      (node (ref "SW1") (pin "CH2B") (pinfunction "CH2B_CH2B") (pintype "bidirectional"))
    )
    (net (code "111") (name "S31") (class "Default")
      (node (ref "H5") (pin "17") (pinfunction "17_17") (pintype "bidirectional"))
      (node (ref "SW2") (pin "CH1A") (pinfunction "CH1A_CH1A") (pintype "bidirectional"))
      (node (ref "SW2") (pin "CH2A") (pinfunction "CH2A_CH2A") (pintype "bidirectional"))
    )
    (net (code "112") (name "S33") (class "Default")
      (node (ref "H5") (pin "15") (pinfunction "15_15") (pintype "bidirectional"))
      (node (ref "SW2") (pin "COM1") (pinfunction "COM1_COM1") (pintype "bidirectional"))
      (node (ref "SW2") (pin "COM2") (pinfunction "COM2_COM2") (pintype "bidirectional"))
    )
    (net (code "113") (name "S35") (class "Default")
      (node (ref "H5") (pin "13") (pinfunction "13_13") (pintype "bidirectional"))
      (node (ref "SW2") (pin "CH1B") (pinfunction "CH1B_CH1B") (pintype "bidirectional"))
      (node (ref "SW2") (pin "CH2B") (pinfunction "CH2B_CH2B") (pintype "bidirectional"))
    )
    (net (code "114") (name "TR1") (class "Default")
      (node (ref "H2") (pin "1") (pinfunction "1_1") (pintype "bidirectional"))
      (node (ref "R73") (pin "1") (pinfunction "1_1") (pintype "passive"))
    )
    (net (code "115") (name "TRB1") (class "Default")
      (node (ref "H1") (pin "6") (pinfunction "6_6") (pintype "bidirectional"))
      (node (ref "Q3") (pin "2") (pinfunction "B_2") (pintype "bidirectional"))
    )
    (net (code "116") (name "TRB2") (class "Default")
      (node (ref "H1") (pin "5") (pinfunction "5_5") (pintype "bidirectional"))
      (node (ref "Q2") (pin "2") (pinfunction "B_2") (pintype "bidirectional"))
    )
    (net (code "117") (name "TRC1") (class "Default")
      (node (ref "H1") (pin "8") (pinfunction "8_8") (pintype "bidirectional"))
      (node (ref "Q3") (pin "3") (pinfunction "C_3") (pintype "bidirectional"))
    )
    (net (code "118") (name "TRC2") (class "Default")
      (node (ref "H1") (pin "7") (pinfunction "7_7") (pintype "bidirectional"))
      (node (ref "Q2") (pin "3") (pinfunction "C_3") (pintype "bidirectional"))
    )
    (net (code "119") (name "TRE1") (class "Default")
      (node (ref "H1") (pin "4") (pinfunction "4_4") (pintype "bidirectional"))
      (node (ref "Q3") (pin "1") (pinfunction "E_1") (pintype "bidirectional"))
    )
    (net (code "120") (name "TRE2") (class "Default")
      (node (ref "H1") (pin "3") (pinfunction "3_3") (pintype "bidirectional"))
      (node (ref "Q2") (pin "1") (pinfunction "E_1") (pintype "bidirectional"))
    )
    (net (code "121") (name "U1-1A") (class "Default")
      (node (ref "H3") (pin "31") (pinfunction "31_31") (pintype "bidirectional"))
      (node (ref "J5") (pin "16") (pinfunction "16_16") (pintype "bidirectional"))
      (node (ref "R80") (pin "1") (pinfunction "1_1") (pintype "passive"))
      (node (ref "U1") (pin "1") (pinfunction "1A_1") (pintype "bidirectional"))
    )
    (net (code "122") (name "U1-1B") (class "Default")
      (node (ref "H3") (pin "29") (pinfunction "29_29") (pintype "bidirectional"))
      (node (ref "J5") (pin "15") (pinfunction "15_15") (pintype "bidirectional"))
      (node (ref "R81") (pin "2") (pinfunction "2_2") (pintype "passive"))
      (node (ref "U1") (pin "2") (pinfunction "1Y_2") (pintype "bidirectional"))
    )
    (net (code "123") (name "U1-1Y") (class "Default")
      (node (ref "H3") (pin "27") (pinfunction "27_27") (pintype "bidirectional"))
      (node (ref "U1") (pin "3") (pinfunction "2A_3") (pintype "bidirectional"))
    )
    (net (code "124") (name "U1-2A") (class "Default")
      (node (ref "H3") (pin "25") (pinfunction "25_25") (pintype "bidirectional"))
      (node (ref "J5") (pin "14") (pinfunction "14_14") (pintype "bidirectional"))
      (node (ref "R82") (pin "1") (pinfunction "1_1") (pintype "passive"))
      (node (ref "U1") (pin "4") (pinfunction "2Y_4") (pintype "bidirectional"))
    )
    (net (code "125") (name "U1-2B") (class "Default")
      (node (ref "H3") (pin "23") (pinfunction "23_23") (pintype "bidirectional"))
      (node (ref "J5") (pin "13") (pinfunction "13_13") (pintype "bidirectional"))
      (node (ref "R83") (pin "1") (pinfunction "1_1") (pintype "passive"))
      (node (ref "U1") (pin "5") (pinfunction "3A_5") (pintype "bidirectional"))
    )
    (net (code "126") (name "U1-2Y") (class "Default")
      (node (ref "H3") (pin "21") (pinfunction "21_21") (pintype "bidirectional"))
      (node (ref "U1") (pin "6") (pinfunction "3Y_6") (pintype "bidirectional"))
    )
    (net (code "127") (name "U1-3A") (class "Default")
      (node (ref "H3") (pin "19") (pinfunction "19_19") (pintype "bidirectional"))
      (node (ref "J5") (pin "9") (pinfunction "9_9") (pintype "bidirectional"))
      (node (ref "R87") (pin "2") (pinfunction "2_2") (pintype "passive"))
      (node (ref "U1") (pin "9") (pinfunction "4A_9") (pintype "bidirectional"))
    )
    (net (code "128") (name "U1-3B") (class "Default")
      (node (ref "H3") (pin "17") (pinfunction "17_17") (pintype "bidirectional"))
      (node (ref "J5") (pin "10") (pinfunction "10_10") (pintype "bidirectional"))
      (node (ref "R86") (pin "2") (pinfunction "2_2") (pintype "passive"))
      (node (ref "U1") (pin "10") (pinfunction "5Y_10") (pintype "bidirectional"))
    )
    (net (code "129") (name "U1-3Y") (class "Default")
      (node (ref "H3") (pin "15") (pinfunction "15_15") (pintype "bidirectional"))
      (node (ref "U1") (pin "8") (pinfunction "4Y_8") (pintype "bidirectional"))
    )
    (net (code "130") (name "U1-4A") (class "Default")
      (node (ref "H3") (pin "13") (pinfunction "13_13") (pintype "bidirectional"))
      (node (ref "J5") (pin "11") (pinfunction "11_11") (pintype "bidirectional"))
      (node (ref "R85") (pin "2") (pinfunction "2_2") (pintype "passive"))
      (node (ref "U1") (pin "12") (pinfunction "6Y_12") (pintype "bidirectional"))
    )
    (net (code "131") (name "U1-4B") (class "Default")
      (node (ref "H3") (pin "11") (pinfunction "11_11") (pintype "bidirectional"))
      (node (ref "J5") (pin "12") (pinfunction "12_12") (pintype "bidirectional"))
      (node (ref "R84") (pin "2") (pinfunction "2_2") (pintype "passive"))
      (node (ref "U1") (pin "13") (pinfunction "6A_13") (pintype "bidirectional"))
    )
    (net (code "132") (name "U1-4Y") (class "Default")
      (node (ref "H3") (pin "9") (pinfunction "9_9") (pintype "bidirectional"))
      (node (ref "U1") (pin "11") (pinfunction "5A_11") (pintype "bidirectional"))
    )
    (net (code "133") (name "U2-1A") (class "Default")
      (node (ref "H2") (pin "31") (pinfunction "31_31") (pintype "bidirectional"))
      (node (ref "J1") (pin "12") (pinfunction "12_12") (pintype "bidirectional"))
      (node (ref "R27") (pin "1") (pinfunction "1_1") (pintype "passive"))
      (node (ref "U2") (pin "1") (pinfunction "1A_1") (pintype "bidirectional"))
    )
    (net (code "134") (name "U2-1Y") (class "Default")
      (node (ref "H2") (pin "29") (pinfunction "29_29") (pintype "bidirectional"))
      (node (ref "U2") (pin "2") (pinfunction "1Y_2") (pintype "bidirectional"))
    )
    (net (code "135") (name "U2-2A") (class "Default")
      (node (ref "H2") (pin "27") (pinfunction "27_27") (pintype "bidirectional"))
      (node (ref "J1") (pin "11") (pinfunction "11_11") (pintype "bidirectional"))
      (node (ref "R26") (pin "1") (pinfunction "1_1") (pintype "passive"))
      (node (ref "U2") (pin "3") (pinfunction "2A_3") (pintype "bidirectional"))
    )
    (net (code "136") (name "U2-2Y") (class "Default")
      (node (ref "H2") (pin "25") (pinfunction "25_25") (pintype "bidirectional"))
      (node (ref "U2") (pin "4") (pinfunction "2Y_4") (pintype "bidirectional"))
    )
    (net (code "137") (name "U2-3A") (class "Default")
      (node (ref "H2") (pin "23") (pinfunction "23_23") (pintype "bidirectional"))
      (node (ref "J1") (pin "10") (pinfunction "10_10") (pintype "bidirectional"))
      (node (ref "R25") (pin "1") (pinfunction "1_1") (pintype "passive"))
      (node (ref "U2") (pin "5") (pinfunction "3A_5") (pintype "bidirectional"))
    )
    (net (code "138") (name "U2-3Y") (class "Default")
      (node (ref "H2") (pin "21") (pinfunction "21_21") (pintype "bidirectional"))
      (node (ref "U2") (pin "6") (pinfunction "3Y_6") (pintype "bidirectional"))
    )
    (net (code "139") (name "U2-4A") (class "Default")
      (node (ref "H2") (pin "19") (pinfunction "19_19") (pintype "bidirectional"))
      (node (ref "J1") (pin "9") (pinfunction "9_9") (pintype "bidirectional"))
      (node (ref "R30") (pin "1") (pinfunction "1_1") (pintype "passive"))
      (node (ref "U2") (pin "9") (pinfunction "4A_9") (pintype "bidirectional"))
    )
    (net (code "140") (name "U2-4Y") (class "Default")
      (node (ref "H2") (pin "17") (pinfunction "17_17") (pintype "bidirectional"))
      (node (ref "U2") (pin "8") (pinfunction "4Y_8") (pintype "bidirectional"))
    )
    (net (code "141") (name "U2-5A") (class "Default")
      (node (ref "H2") (pin "15") (pinfunction "15_15") (pintype "bidirectional"))
      (node (ref "J1") (pin "8") (pinfunction "8_8") (pintype "bidirectional"))
      (node (ref "R29") (pin "1") (pinfunction "1_1") (pintype "passive"))
      (node (ref "U2") (pin "11") (pinfunction "5A_11") (pintype "bidirectional"))
    )
    (net (code "142") (name "U2-5Y") (class "Default")
      (node (ref "H2") (pin "13") (pinfunction "13_13") (pintype "bidirectional"))
      (node (ref "U2") (pin "10") (pinfunction "5Y_10") (pintype "bidirectional"))
    )
    (net (code "143") (name "U2-6A") (class "Default")
      (node (ref "H2") (pin "11") (pinfunction "11_11") (pintype "bidirectional"))
      (node (ref "J1") (pin "7") (pinfunction "7_7") (pintype "bidirectional"))
      (node (ref "R28") (pin "1") (pinfunction "1_1") (pintype "passive"))
      (node (ref "U2") (pin "13") (pinfunction "6A_13") (pintype "bidirectional"))
    )
    (net (code "144") (name "U2-6Y") (class "Default")
      (node (ref "H2") (pin "9") (pinfunction "9_9") (pintype "bidirectional"))
      (node (ref "U2") (pin "12") (pinfunction "6Y_12") (pintype "bidirectional"))
    )
    (net (code "145") (name "U3-1A") (class "Default")
      (node (ref "H2") (pin "32") (pinfunction "32_32") (pintype "bidirectional"))
      (node (ref "J2") (pin "12") (pinfunction "12_12") (pintype "bidirectional"))
      (node (ref "R21") (pin "1") (pinfunction "1_1") (pintype "passive"))
      (node (ref "U3") (pin "1") (pinfunction "1A_1") (pintype "bidirectional"))
    )
    (net (code "146") (name "U3-1Y") (class "Default")
      (node (ref "H2") (pin "30") (pinfunction "30_30") (pintype "bidirectional"))
      (node (ref "U3") (pin "2") (pinfunction "1Y_2") (pintype "bidirectional"))
    )
    (net (code "147") (name "U3-2A") (class "Default")
      (node (ref "H2") (pin "28") (pinfunction "28_28") (pintype "bidirectional"))
      (node (ref "J2") (pin "11") (pinfunction "11_11") (pintype "bidirectional"))
      (node (ref "R20") (pin "1") (pinfunction "1_1") (pintype "passive"))
      (node (ref "U3") (pin "3") (pinfunction "2A_3") (pintype "bidirectional"))
    )
    (net (code "148") (name "U3-2Y") (class "Default")
      (node (ref "H2") (pin "26") (pinfunction "26_26") (pintype "bidirectional"))
      (node (ref "U3") (pin "4") (pinfunction "2Y_4") (pintype "bidirectional"))
    )
    (net (code "149") (name "U3-3A") (class "Default")
      (node (ref "H2") (pin "24") (pinfunction "24_24") (pintype "bidirectional"))
      (node (ref "J2") (pin "10") (pinfunction "10_10") (pintype "bidirectional"))
      (node (ref "R19") (pin "1") (pinfunction "1_1") (pintype "passive"))
      (node (ref "U3") (pin "5") (pinfunction "3A_5") (pintype "bidirectional"))
    )
    (net (code "150") (name "U3-3Y") (class "Default")
      (node (ref "H2") (pin "22") (pinfunction "22_22") (pintype "bidirectional"))
      (node (ref "U3") (pin "6") (pinfunction "3Y_6") (pintype "bidirectional"))
    )
    (net (code "151") (name "U3-4A") (class "Default")
      (node (ref "H2") (pin "20") (pinfunction "20_20") (pintype "bidirectional"))
      (node (ref "J2") (pin "9") (pinfunction "9_9") (pintype "bidirectional"))
      (node (ref "R24") (pin "1") (pinfunction "1_1") (pintype "passive"))
      (node (ref "U3") (pin "9") (pinfunction "4A_9") (pintype "bidirectional"))
    )
    (net (code "152") (name "U3-4Y") (class "Default")
      (node (ref "H2") (pin "18") (pinfunction "18_18") (pintype "bidirectional"))
      (node (ref "U3") (pin "8") (pinfunction "4Y_8") (pintype "bidirectional"))
    )
    (net (code "153") (name "U3-5A") (class "Default")
      (node (ref "H2") (pin "16") (pinfunction "16_16") (pintype "bidirectional"))
      (node (ref "J2") (pin "8") (pinfunction "8_8") (pintype "bidirectional"))
      (node (ref "R23") (pin "1") (pinfunction "1_1") (pintype "passive"))
      (node (ref "U3") (pin "11") (pinfunction "5A_11") (pintype "bidirectional"))
    )
    (net (code "154") (name "U3-5Y") (class "Default")
      (node (ref "H2") (pin "14") (pinfunction "14_14") (pintype "bidirectional"))
      (node (ref "U3") (pin "10") (pinfunction "5Y_10") (pintype "bidirectional"))
    )
    (net (code "155") (name "U3-6A") (class "Default")
      (node (ref "H2") (pin "12") (pinfunction "12_12") (pintype "bidirectional"))
      (node (ref "J2") (pin "7") (pinfunction "7_7") (pintype "bidirectional"))
      (node (ref "R22") (pin "1") (pinfunction "1_1") (pintype "passive"))
      (node (ref "U3") (pin "13") (pinfunction "6A_13") (pintype "bidirectional"))
    )
    (net (code "156") (name "U3-6Y") (class "Default")
      (node (ref "H2") (pin "10") (pinfunction "10_10") (pintype "bidirectional"))
      (node (ref "U3") (pin "12") (pinfunction "6Y_12") (pintype "bidirectional"))
    )
    (net (code "157") (name "U4-1A") (class "Default")
      (node (ref "H1") (pin "32") (pinfunction "32_32") (pintype "bidirectional"))
      (node (ref "J7") (pin "16") (pinfunction "16_16") (pintype "bidirectional"))
      (node (ref "R31") (pin "1") (pinfunction "1_1") (pintype "passive"))
      (node (ref "U4") (pin "1") (pinfunction "1A_1") (pintype "bidirectional"))
    )
    (net (code "158") (name "U4-1B") (class "Default")
      (node (ref "H1") (pin "30") (pinfunction "30_30") (pintype "bidirectional"))
      (node (ref "J7") (pin "15") (pinfunction "15_15") (pintype "bidirectional"))
      (node (ref "R32") (pin "2") (pinfunction "2_2") (pintype "passive"))
      (node (ref "U4") (pin "2") (pinfunction "1B_2") (pintype "bidirectional"))
    )
    (net (code "159") (name "U4-1Y") (class "Default")
      (node (ref "H1") (pin "28") (pinfunction "28_28") (pintype "bidirectional"))
      (node (ref "U4") (pin "3") (pinfunction "1Y_3") (pintype "bidirectional"))
    )
    (net (code "160") (name "U4-2A") (class "Default")
      (node (ref "H1") (pin "26") (pinfunction "26_26") (pintype "bidirectional"))
      (node (ref "J7") (pin "14") (pinfunction "14_14") (pintype "bidirectional"))
      (node (ref "R33") (pin "1") (pinfunction "1_1") (pintype "passive"))
      (node (ref "U4") (pin "4") (pinfunction "2A_4") (pintype "bidirectional"))
    )
    (net (code "161") (name "U4-2B") (class "Default")
      (node (ref "H1") (pin "24") (pinfunction "24_24") (pintype "bidirectional"))
      (node (ref "J7") (pin "13") (pinfunction "13_13") (pintype "bidirectional"))
      (node (ref "R34") (pin "1") (pinfunction "1_1") (pintype "passive"))
      (node (ref "U4") (pin "5") (pinfunction "2B_5") (pintype "bidirectional"))
    )
    (net (code "162") (name "U4-2Y") (class "Default")
      (node (ref "H1") (pin "22") (pinfunction "22_22") (pintype "bidirectional"))
      (node (ref "U4") (pin "6") (pinfunction "2Y_6") (pintype "bidirectional"))
    )
    (net (code "163") (name "U4-3A") (class "Default")
      (node (ref "H1") (pin "20") (pinfunction "20_20") (pintype "bidirectional"))
      (node (ref "J7") (pin "9") (pinfunction "9_9") (pintype "bidirectional"))
      (node (ref "R38") (pin "2") (pinfunction "2_2") (pintype "passive"))
      (node (ref "U4") (pin "9") (pinfunction "3A_9") (pintype "bidirectional"))
    )
    (net (code "164") (name "U4-3B") (class "Default")
      (node (ref "H1") (pin "18") (pinfunction "18_18") (pintype "bidirectional"))
      (node (ref "J7") (pin "10") (pinfunction "10_10") (pintype "bidirectional"))
      (node (ref "R37") (pin "2") (pinfunction "2_2") (pintype "passive"))
      (node (ref "U4") (pin "10") (pinfunction "3B_10") (pintype "bidirectional"))
    )
    (net (code "165") (name "U4-3Y") (class "Default")
      (node (ref "H1") (pin "16") (pinfunction "16_16") (pintype "bidirectional"))
      (node (ref "U4") (pin "8") (pinfunction "3Y_8") (pintype "bidirectional"))
    )
    (net (code "166") (name "U4-4A") (class "Default")
      (node (ref "H1") (pin "14") (pinfunction "14_14") (pintype "bidirectional"))
      (node (ref "J7") (pin "11") (pinfunction "11_11") (pintype "bidirectional"))
      (node (ref "R36") (pin "2") (pinfunction "2_2") (pintype "passive"))
      (node (ref "U4") (pin "12") (pinfunction "4A_12") (pintype "bidirectional"))
    )
    (net (code "167") (name "U4-4B") (class "Default")
      (node (ref "H1") (pin "12") (pinfunction "12_12") (pintype "bidirectional"))
      (node (ref "J7") (pin "12") (pinfunction "12_12") (pintype "bidirectional"))
      (node (ref "R35") (pin "2") (pinfunction "2_2") (pintype "passive"))
      (node (ref "U4") (pin "13") (pinfunction "4B_13") (pintype "bidirectional"))
    )
    (net (code "168") (name "U4-4Y") (class "Default")
      (node (ref "H1") (pin "10") (pinfunction "10_10") (pintype "bidirectional"))
      (node (ref "U4") (pin "11") (pinfunction "4Y_11") (pintype "bidirectional"))
    )
    (net (code "169") (name "U5-1A") (class "Default")
      (node (ref "H1") (pin "31") (pinfunction "31_31") (pintype "bidirectional"))
      (node (ref "J8") (pin "16") (pinfunction "16_16") (pintype "bidirectional"))
      (node (ref "R39") (pin "1") (pinfunction "1_1") (pintype "passive"))
      (node (ref "U5") (pin "1") (pinfunction "1A_1") (pintype "bidirectional"))
    )
    (net (code "170") (name "U5-1B") (class "Default")
      (node (ref "H1") (pin "29") (pinfunction "29_29") (pintype "bidirectional"))
      (node (ref "J8") (pin "15") (pinfunction "15_15") (pintype "bidirectional"))
      (node (ref "R40") (pin "2") (pinfunction "2_2") (pintype "passive"))
      (node (ref "U5") (pin "2") (pinfunction "1B_2") (pintype "bidirectional"))
    )
    (net (code "171") (name "U5-1Y") (class "Default")
      (node (ref "H1") (pin "27") (pinfunction "27_27") (pintype "bidirectional"))
      (node (ref "U5") (pin "3") (pinfunction "1Y_3") (pintype "bidirectional"))
    )
    (net (code "172") (name "U5-2A") (class "Default")
      (node (ref "H1") (pin "25") (pinfunction "25_25") (pintype "bidirectional"))
      (node (ref "J8") (pin "14") (pinfunction "14_14") (pintype "bidirectional"))
      (node (ref "R41") (pin "1") (pinfunction "1_1") (pintype "passive"))
      (node (ref "U5") (pin "4") (pinfunction "2A_4") (pintype "bidirectional"))
    )
    (net (code "173") (name "U5-2B") (class "Default")
      (node (ref "H1") (pin "23") (pinfunction "23_23") (pintype "bidirectional"))
      (node (ref "J8") (pin "13") (pinfunction "13_13") (pintype "bidirectional"))
      (node (ref "R42") (pin "1") (pinfunction "1_1") (pintype "passive"))
      (node (ref "U5") (pin "5") (pinfunction "2B_5") (pintype "bidirectional"))
    )
    (net (code "174") (name "U5-2Y") (class "Default")
      (node (ref "H1") (pin "21") (pinfunction "21_21") (pintype "bidirectional"))
      (node (ref "U5") (pin "6") (pinfunction "2Y_6") (pintype "bidirectional"))
    )
    (net (code "175") (name "U5-3A") (class "Default")
      (node (ref "H1") (pin "19") (pinfunction "19_19") (pintype "bidirectional"))
      (node (ref "J8") (pin "9") (pinfunction "9_9") (pintype "bidirectional"))
      (node (ref "R46") (pin "2") (pinfunction "2_2") (pintype "passive"))
      (node (ref "U5") (pin "9") (pinfunction "3A_9") (pintype "bidirectional"))
    )
    (net (code "176") (name "U5-3B") (class "Default")
      (node (ref "H1") (pin "17") (pinfunction "17_17") (pintype "bidirectional"))
      (node (ref "J8") (pin "10") (pinfunction "10_10") (pintype "bidirectional"))
      (node (ref "R45") (pin "2") (pinfunction "2_2") (pintype "passive"))
      (node (ref "U5") (pin "10") (pinfunction "3B_10") (pintype "bidirectional"))
    )
    (net (code "177") (name "U5-3Y") (class "Default")
      (node (ref "H1") (pin "15") (pinfunction "15_15") (pintype "bidirectional"))
      (node (ref "U5") (pin "8") (pinfunction "3Y_8") (pintype "bidirectional"))
    )
    (net (code "178") (name "U5-4A") (class "Default")
      (node (ref "H1") (pin "13") (pinfunction "13_13") (pintype "bidirectional"))
      (node (ref "J8") (pin "11") (pinfunction "11_11") (pintype "bidirectional"))
      (node (ref "R44") (pin "2") (pinfunction "2_2") (pintype "passive"))
      (node (ref "U5") (pin "12") (pinfunction "4A_12") (pintype "bidirectional"))
    )
    (net (code "179") (name "U5-4B") (class "Default")
      (node (ref "H1") (pin "11") (pinfunction "11_11") (pintype "bidirectional"))
      (node (ref "J8") (pin "12") (pinfunction "12_12") (pintype "bidirectional"))
      (node (ref "R43") (pin "2") (pinfunction "2_2") (pintype "passive"))
      (node (ref "U5") (pin "13") (pinfunction "4B_13") (pintype "bidirectional"))
    )
    (net (code "180") (name "U5-4Y") (class "Default")
      (node (ref "H1") (pin "9") (pinfunction "9_9") (pintype "bidirectional"))
      (node (ref "U5") (pin "11") (pinfunction "4Y_11") (pintype "bidirectional"))
    )
    (net (code "181") (name "U6-1A") (class "Default")
      (node (ref "H3") (pin "32") (pinfunction "32_32") (pintype "bidirectional"))
      (node (ref "J4") (pin "16") (pinfunction "16_16") (pintype "bidirectional"))
      (node (ref "R47") (pin "1") (pinfunction "1_1") (pintype "passive"))
      (node (ref "U6") (pin "1") (pinfunction "1A_1") (pintype "bidirectional"))
    )
    (net (code "182") (name "U6-1B") (class "Default")
      (node (ref "H3") (pin "30") (pinfunction "30_30") (pintype "bidirectional"))
      (node (ref "J4") (pin "15") (pinfunction "15_15") (pintype "bidirectional"))
      (node (ref "R48") (pin "2") (pinfunction "2_2") (pintype "passive"))
      (node (ref "U6") (pin "2") (pinfunction "1Y_2") (pintype "bidirectional"))
    )
    (net (code "183") (name "U6-1Y") (class "Default")
      (node (ref "H3") (pin "28") (pinfunction "28_28") (pintype "bidirectional"))
      (node (ref "U6") (pin "3") (pinfunction "2A_3") (pintype "bidirectional"))
    )
    (net (code "184") (name "U6-2A") (class "Default")
      (node (ref "H3") (pin "26") (pinfunction "26_26") (pintype "bidirectional"))
      (node (ref "J4") (pin "14") (pinfunction "14_14") (pintype "bidirectional"))
      (node (ref "R49") (pin "1") (pinfunction "1_1") (pintype "passive"))
      (node (ref "U6") (pin "4") (pinfunction "2Y_4") (pintype "bidirectional"))
    )
    (net (code "185") (name "U6-2B") (class "Default")
      (node (ref "H3") (pin "24") (pinfunction "24_24") (pintype "bidirectional"))
      (node (ref "J4") (pin "13") (pinfunction "13_13") (pintype "bidirectional"))
      (node (ref "R50") (pin "1") (pinfunction "1_1") (pintype "passive"))
      (node (ref "U6") (pin "5") (pinfunction "3A_5") (pintype "bidirectional"))
    )
    (net (code "186") (name "U6-2Y") (class "Default")
      (node (ref "H3") (pin "22") (pinfunction "22_22") (pintype "bidirectional"))
      (node (ref "U6") (pin "6") (pinfunction "3Y_6") (pintype "bidirectional"))
    )
    (net (code "187") (name "U6-3A") (class "Default")
      (node (ref "H3") (pin "20") (pinfunction "20_20") (pintype "bidirectional"))
      (node (ref "J4") (pin "9") (pinfunction "9_9") (pintype "bidirectional"))
      (node (ref "R54") (pin "2") (pinfunction "2_2") (pintype "passive"))
      (node (ref "U6") (pin "9") (pinfunction "4A_9") (pintype "bidirectional"))
    )
    (net (code "188") (name "U6-3B") (class "Default")
      (node (ref "H3") (pin "18") (pinfunction "18_18") (pintype "bidirectional"))
      (node (ref "J4") (pin "10") (pinfunction "10_10") (pintype "bidirectional"))
      (node (ref "R53") (pin "2") (pinfunction "2_2") (pintype "passive"))
      (node (ref "U6") (pin "10") (pinfunction "5Y_10") (pintype "bidirectional"))
    )
    (net (code "189") (name "U6-3Y") (class "Default")
      (node (ref "H3") (pin "16") (pinfunction "16_16") (pintype "bidirectional"))
      (node (ref "U6") (pin "8") (pinfunction "4Y_8") (pintype "bidirectional"))
    )
    (net (code "190") (name "U6-4A") (class "Default")
      (node (ref "H3") (pin "14") (pinfunction "14_14") (pintype "bidirectional"))
      (node (ref "J4") (pin "11") (pinfunction "11_11") (pintype "bidirectional"))
      (node (ref "R52") (pin "2") (pinfunction "2_2") (pintype "passive"))
      (node (ref "U6") (pin "12") (pinfunction "6Y_12") (pintype "bidirectional"))
    )
    (net (code "191") (name "U6-4B") (class "Default")
      (node (ref "H3") (pin "12") (pinfunction "12_12") (pintype "bidirectional"))
      (node (ref "J4") (pin "12") (pinfunction "12_12") (pintype "bidirectional"))
      (node (ref "R51") (pin "2") (pinfunction "2_2") (pintype "passive"))
      (node (ref "U6") (pin "13") (pinfunction "6A_13") (pintype "bidirectional"))
    )
    (net (code "192") (name "U6-4Y") (class "Default")
      (node (ref "H3") (pin "10") (pinfunction "10_10") (pintype "bidirectional"))
      (node (ref "U6") (pin "11") (pinfunction "5A_11") (pintype "bidirectional"))
    )
    (net (code "193") (name "U7-DIS") (class "Default")
      (node (ref "H2") (pin "4") (pinfunction "4_4") (pintype "bidirectional"))
      (node (ref "U7") (pin "7") (pinfunction "DISCH_7") (pintype "bidirectional"))
    )
    (net (code "194") (name "U7-OUT") (class "Default")
      (node (ref "H2") (pin "6") (pinfunction "6_6") (pintype "bidirectional"))
      (node (ref "U7") (pin "3") (pinfunction "OUT_3") (pintype "output"))
    )
    (net (code "195") (name "U7-THR") (class "Default")
      (node (ref "H2") (pin "2") (pinfunction "2_2") (pintype "bidirectional"))
      (node (ref "U7") (pin "6") (pinfunction "THRES_6") (pintype "bidirectional"))
    )
    (net (code "196") (name "U7-TR") (class "Default")
      (node (ref "H2") (pin "8") (pinfunction "8_8") (pintype "bidirectional"))
      (node (ref "U7") (pin "2") (pinfunction "TRIG_2") (pintype "bidirectional"))
    )
    (net (code "197") (name "U8-1A") (class "Default")
      (node (ref "H4") (pin "31") (pinfunction "31_31") (pintype "bidirectional"))
      (node (ref "J6") (pin "16") (pinfunction "16_16") (pintype "bidirectional"))
      (node (ref "R55") (pin "1") (pinfunction "1_1") (pintype "passive"))
      (node (ref "U8") (pin "1") (pinfunction "1A_1") (pintype "bidirectional"))
    )
    (net (code "198") (name "U8-1B") (class "Default")
      (node (ref "H4") (pin "29") (pinfunction "29_29") (pintype "bidirectional"))
      (node (ref "J6") (pin "15") (pinfunction "15_15") (pintype "bidirectional"))
      (node (ref "R56") (pin "2") (pinfunction "2_2") (pintype "passive"))
      (node (ref "U8") (pin "2") (pinfunction "1B_2") (pintype "bidirectional"))
    )
    (net (code "199") (name "U8-1Y") (class "Default")
      (node (ref "H4") (pin "27") (pinfunction "27_27") (pintype "bidirectional"))
      (node (ref "U8") (pin "3") (pinfunction "1Y_3") (pintype "bidirectional"))
    )
    (net (code "200") (name "U8-2A") (class "Default")
      (node (ref "H4") (pin "25") (pinfunction "25_25") (pintype "bidirectional"))
      (node (ref "J6") (pin "14") (pinfunction "14_14") (pintype "bidirectional"))
      (node (ref "R57") (pin "1") (pinfunction "1_1") (pintype "passive"))
      (node (ref "U8") (pin "4") (pinfunction "2A_4") (pintype "bidirectional"))
    )
    (net (code "201") (name "U8-2B") (class "Default")
      (node (ref "H4") (pin "23") (pinfunction "23_23") (pintype "bidirectional"))
      (node (ref "J6") (pin "13") (pinfunction "13_13") (pintype "bidirectional"))
      (node (ref "R58") (pin "1") (pinfunction "1_1") (pintype "passive"))
      (node (ref "U8") (pin "5") (pinfunction "2B_5") (pintype "bidirectional"))
    )
    (net (code "202") (name "U8-2Y") (class "Default")
      (node (ref "H4") (pin "21") (pinfunction "21_21") (pintype "bidirectional"))
      (node (ref "U8") (pin "6") (pinfunction "2Y_6") (pintype "bidirectional"))
    )
    (net (code "203") (name "U8-3A") (class "Default")
      (node (ref "H4") (pin "19") (pinfunction "19_19") (pintype "bidirectional"))
      (node (ref "J6") (pin "9") (pinfunction "9_9") (pintype "bidirectional"))
      (node (ref "R62") (pin "2") (pinfunction "2_2") (pintype "passive"))
      (node (ref "U8") (pin "9") (pinfunction "3A_9") (pintype "bidirectional"))
    )
    (net (code "204") (name "U8-3B") (class "Default")
      (node (ref "H4") (pin "17") (pinfunction "17_17") (pintype "bidirectional"))
      (node (ref "J6") (pin "10") (pinfunction "10_10") (pintype "bidirectional"))
      (node (ref "R61") (pin "2") (pinfunction "2_2") (pintype "passive"))
      (node (ref "U8") (pin "10") (pinfunction "3B_10") (pintype "bidirectional"))
    )
    (net (code "205") (name "U8-3Y") (class "Default")
      (node (ref "H4") (pin "15") (pinfunction "15_15") (pintype "bidirectional"))
      (node (ref "U8") (pin "8") (pinfunction "3Y_8") (pintype "bidirectional"))
    )
    (net (code "206") (name "U8-4A") (class "Default")
      (node (ref "H4") (pin "13") (pinfunction "13_13") (pintype "bidirectional"))
      (node (ref "J6") (pin "11") (pinfunction "11_11") (pintype "bidirectional"))
      (node (ref "R60") (pin "2") (pinfunction "2_2") (pintype "passive"))
      (node (ref "U8") (pin "12") (pinfunction "4A_12") (pintype "bidirectional"))
    )
    (net (code "207") (name "U8-4B") (class "Default")
      (node (ref "H4") (pin "11") (pinfunction "11_11") (pintype "bidirectional"))
      (node (ref "J6") (pin "12") (pinfunction "12_12") (pintype "bidirectional"))
      (node (ref "R59") (pin "2") (pinfunction "2_2") (pintype "passive"))
      (node (ref "U8") (pin "13") (pinfunction "4B_13") (pintype "bidirectional"))
    )
    (net (code "208") (name "U8-4Y") (class "Default")
      (node (ref "H4") (pin "9") (pinfunction "9_9") (pintype "bidirectional"))
      (node (ref "U8") (pin "11") (pinfunction "4Y_11") (pintype "bidirectional"))
    )
    (net (code "209") (name "U9-1A") (class "Default")
      (node (ref "H4") (pin "32") (pinfunction "32_32") (pintype "bidirectional"))
      (node (ref "J3") (pin "16") (pinfunction "16_16") (pintype "bidirectional"))
      (node (ref "R63") (pin "1") (pinfunction "1_1") (pintype "passive"))
      (node (ref "U9") (pin "1") (pinfunction "1A_1") (pintype "bidirectional"))
    )
    (net (code "210") (name "U9-1B") (class "Default")
      (node (ref "H4") (pin "30") (pinfunction "30_30") (pintype "bidirectional"))
      (node (ref "J3") (pin "15") (pinfunction "15_15") (pintype "bidirectional"))
      (node (ref "R64") (pin "2") (pinfunction "2_2") (pintype "passive"))
      (node (ref "U9") (pin "2") (pinfunction "1B_2") (pintype "bidirectional"))
    )
    (net (code "211") (name "U9-1Y") (class "Default")
      (node (ref "H4") (pin "28") (pinfunction "28_28") (pintype "bidirectional"))
      (node (ref "U9") (pin "3") (pinfunction "1Y_3") (pintype "bidirectional"))
    )
    (net (code "212") (name "U9-2A") (class "Default")
      (node (ref "H4") (pin "26") (pinfunction "26_26") (pintype "bidirectional"))
      (node (ref "J3") (pin "14") (pinfunction "14_14") (pintype "bidirectional"))
      (node (ref "R65") (pin "1") (pinfunction "1_1") (pintype "passive"))
      (node (ref "U9") (pin "4") (pinfunction "2A_4") (pintype "bidirectional"))
    )
    (net (code "213") (name "U9-2B") (class "Default")
      (node (ref "H4") (pin "24") (pinfunction "24_24") (pintype "bidirectional"))
      (node (ref "J3") (pin "13") (pinfunction "13_13") (pintype "bidirectional"))
      (node (ref "R66") (pin "1") (pinfunction "1_1") (pintype "passive"))
      (node (ref "U9") (pin "5") (pinfunction "2B_5") (pintype "bidirectional"))
    )
    (net (code "214") (name "U9-2Y") (class "Default")
      (node (ref "H4") (pin "22") (pinfunction "22_22") (pintype "bidirectional"))
      (node (ref "U9") (pin "6") (pinfunction "2Y_6") (pintype "bidirectional"))
    )
    (net (code "215") (name "U9-3A") (class "Default")
      (node (ref "H4") (pin "20") (pinfunction "20_20") (pintype "bidirectional"))
      (node (ref "J3") (pin "9") (pinfunction "9_9") (pintype "bidirectional"))
      (node (ref "R70") (pin "2") (pinfunction "2_2") (pintype "passive"))
      (node (ref "U9") (pin "9") (pinfunction "3A_9") (pintype "bidirectional"))
    )
    (net (code "216") (name "U9-3B") (class "Default")
      (node (ref "H4") (pin "18") (pinfunction "18_18") (pintype "bidirectional"))
      (node (ref "J3") (pin "10") (pinfunction "10_10") (pintype "bidirectional"))
      (node (ref "R69") (pin "2") (pinfunction "2_2") (pintype "passive"))
      (node (ref "U9") (pin "10") (pinfunction "3B_10") (pintype "bidirectional"))
    )
    (net (code "217") (name "U9-3Y") (class "Default")
      (node (ref "H4") (pin "16") (pinfunction "16_16") (pintype "bidirectional"))
      (node (ref "U9") (pin "8") (pinfunction "3Y_8") (pintype "bidirectional"))
    )
    (net (code "218") (name "U9-4A") (class "Default")
      (node (ref "H4") (pin "14") (pinfunction "14_14") (pintype "bidirectional"))
      (node (ref "J3") (pin "11") (pinfunction "11_11") (pintype "bidirectional"))
      (node (ref "R68") (pin "2") (pinfunction "2_2") (pintype "passive"))
      (node (ref "U9") (pin "12") (pinfunction "4A_12") (pintype "bidirectional"))
    )
    (net (code "219") (name "U9-4B") (class "Default")
      (node (ref "H4") (pin "12") (pinfunction "12_12") (pintype "bidirectional"))
      (node (ref "J3") (pin "12") (pinfunction "12_12") (pintype "bidirectional"))
      (node (ref "R67") (pin "2") (pinfunction "2_2") (pintype "passive"))
      (node (ref "U9") (pin "13") (pinfunction "4B_13") (pintype "bidirectional"))
    )
    (net (code "220") (name "U9-4Y") (class "Default")
      (node (ref "H4") (pin "10") (pinfunction "10_10") (pintype "bidirectional"))
      (node (ref "U9") (pin "11") (pinfunction "4Y_11") (pintype "bidirectional"))
    )
    (net (code "221") (name "VCC") (class "Default")
      (node (ref "C10") (pin "1") (pinfunction "1_1") (pintype "passive"))
      (node (ref "C11") (pin "1") (pinfunction "1_1") (pintype "passive"))
      (node (ref "C2") (pin "1") (pinfunction "1_1") (pintype "passive"))
      (node (ref "C22") (pin "2") (pinfunction "2_2") (pintype "passive"))
      (node (ref "C27") (pin "2") (pinfunction "2_2") (pintype "passive"))
      (node (ref "C28") (pin "1") (pinfunction "1_1") (pintype "passive"))
      (node (ref "C4") (pin "1") (pinfunction "1_1") (pintype "passive"))
      (node (ref "C5") (pin "1") (pinfunction "1_1") (pintype "passive"))
      (node (ref "C6") (pin "1") (pinfunction "1_1") (pintype "passive"))
      (node (ref "C7") (pin "1") (pinfunction "1_1") (pintype "passive"))
      (node (ref "C9") (pin "1") (pinfunction "1_1") (pintype "passive"))
      (node (ref "H8") (pin "20") (pinfunction "20_20") (pintype "bidirectional"))
      (node (ref "H8") (pin "22") (pinfunction "22_22") (pintype "bidirectional"))
      (node (ref "H8") (pin "24") (pinfunction "24_24") (pintype "bidirectional"))
      (node (ref "H8") (pin "26") (pinfunction "26_26") (pintype "bidirectional"))
      (node (ref "H8") (pin "28") (pinfunction "28_28") (pintype "bidirectional"))
      (node (ref "H8") (pin "30") (pinfunction "30_30") (pintype "bidirectional"))
      (node (ref "H8") (pin "32") (pinfunction "32_32") (pintype "bidirectional"))
      (node (ref "IC1") (pin "5") (pinfunction "VCC_5") (pintype "bidirectional"))
      (node (ref "IC3") (pin "1") (pinfunction "OUT_1") (pintype "bidirectional"))
      (node (ref "LS1") (pin "1") (pinfunction "1_1") (pintype "bidirectional"))
      (node (ref "R19") (pin "2") (pinfunction "2_2") (pintype "passive"))
      (node (ref "R20") (pin "2") (pinfunction "2_2") (pintype "passive"))
      (node (ref "R21") (pin "2") (pinfunction "2_2") (pintype "passive"))
      (node (ref "R22") (pin "2") (pinfunction "2_2") (pintype "passive"))
      (node (ref "R23") (pin "2") (pinfunction "2_2") (pintype "passive"))
      (node (ref "R24") (pin "2") (pinfunction "2_2") (pintype "passive"))
      (node (ref "R25") (pin "2") (pinfunction "2_2") (pintype "passive"))
      (node (ref "R26") (pin "2") (pinfunction "2_2") (pintype "passive"))
      (node (ref "R27") (pin "2") (pinfunction "2_2") (pintype "passive"))
      (node (ref "R28") (pin "2") (pinfunction "2_2") (pintype "passive"))
      (node (ref "R29") (pin "2") (pinfunction "2_2") (pintype "passive"))
      (node (ref "R30") (pin "2") (pinfunction "2_2") (pintype "passive"))
      (node (ref "R31") (pin "2") (pinfunction "2_2") (pintype "passive"))
      (node (ref "R32") (pin "1") (pinfunction "1_1") (pintype "passive"))
      (node (ref "R33") (pin "2") (pinfunction "2_2") (pintype "passive"))
      (node (ref "R34") (pin "2") (pinfunction "2_2") (pintype "passive"))
      (node (ref "R35") (pin "1") (pinfunction "1_1") (pintype "passive"))
      (node (ref "R36") (pin "1") (pinfunction "1_1") (pintype "passive"))
      (node (ref "R37") (pin "1") (pinfunction "1_1") (pintype "passive"))
      (node (ref "R38") (pin "1") (pinfunction "1_1") (pintype "passive"))
      (node (ref "R39") (pin "2") (pinfunction "2_2") (pintype "passive"))
      (node (ref "R40") (pin "1") (pinfunction "1_1") (pintype "passive"))
      (node (ref "R41") (pin "2") (pinfunction "2_2") (pintype "passive"))
      (node (ref "R42") (pin "2") (pinfunction "2_2") (pintype "passive"))
      (node (ref "R43") (pin "1") (pinfunction "1_1") (pintype "passive"))
      (node (ref "R44") (pin "1") (pinfunction "1_1") (pintype "passive"))
      (node (ref "R45") (pin "1") (pinfunction "1_1") (pintype "passive"))
      (node (ref "R46") (pin "1") (pinfunction "1_1") (pintype "passive"))
      (node (ref "R47") (pin "2") (pinfunction "2_2") (pintype "passive"))
      (node (ref "R48") (pin "1") (pinfunction "1_1") (pintype "passive"))
      (node (ref "R49") (pin "2") (pinfunction "2_2") (pintype "passive"))
      (node (ref "R50") (pin "2") (pinfunction "2_2") (pintype "passive"))
      (node (ref "R51") (pin "1") (pinfunction "1_1") (pintype "passive"))
      (node (ref "R52") (pin "1") (pinfunction "1_1") (pintype "passive"))
      (node (ref "R53") (pin "1") (pinfunction "1_1") (pintype "passive"))
      (node (ref "R54") (pin "1") (pinfunction "1_1") (pintype "passive"))
      (node (ref "R55") (pin "2") (pinfunction "2_2") (pintype "passive"))
      (node (ref "R56") (pin "1") (pinfunction "1_1") (pintype "passive"))
      (node (ref "R57") (pin "2") (pinfunction "2_2") (pintype "passive"))
      (node (ref "R58") (pin "2") (pinfunction "2_2") (pintype "passive"))
      (node (ref "R59") (pin "1") (pinfunction "1_1") (pintype "passive"))
      (node (ref "R60") (pin "1") (pinfunction "1_1") (pintype "passive"))
      (node (ref "R61") (pin "1") (pinfunction "1_1") (pintype "passive"))
      (node (ref "R62") (pin "1") (pinfunction "1_1") (pintype "passive"))
      (node (ref "R63") (pin "2") (pinfunction "2_2") (pintype "passive"))
      (node (ref "R64") (pin "1") (pinfunction "1_1") (pintype "passive"))
      (node (ref "R65") (pin "2") (pinfunction "2_2") (pintype "passive"))
      (node (ref "R66") (pin "2") (pinfunction "2_2") (pintype "passive"))
      (node (ref "R67") (pin "1") (pinfunction "1_1") (pintype "passive"))
      (node (ref "R68") (pin "1") (pinfunction "1_1") (pintype "passive"))
      (node (ref "R69") (pin "1") (pinfunction "1_1") (pintype "passive"))
      (node (ref "R70") (pin "1") (pinfunction "1_1") (pintype "passive"))
      (node (ref "R71") (pin "1") (pinfunction "1_1") (pintype "passive"))
      (node (ref "R74") (pin "2") (pinfunction "2_2") (pintype "passive"))
      (node (ref "R79") (pin "1") (pinfunction "1_1") (pintype "passive"))
      (node (ref "R80") (pin "2") (pinfunction "2_2") (pintype "passive"))
      (node (ref "R81") (pin "1") (pinfunction "1_1") (pintype "passive"))
      (node (ref "R82") (pin "2") (pinfunction "2_2") (pintype "passive"))
      (node (ref "R83") (pin "2") (pinfunction "2_2") (pintype "passive"))
      (node (ref "R84") (pin "1") (pinfunction "1_1") (pintype "passive"))
      (node (ref "R85") (pin "1") (pinfunction "1_1") (pintype "passive"))
      (node (ref "R86") (pin "1") (pinfunction "1_1") (pintype "passive"))
      (node (ref "R87") (pin "1") (pinfunction "1_1") (pintype "passive"))
      (node (ref "U1") (pin "14") (pinfunction "VCC_14") (pintype "bidirectional"))
      (node (ref "U2") (pin "14") (pinfunction "VCC_14") (pintype "bidirectional"))
      (node (ref "U3") (pin "14") (pinfunction "VCC_14") (pintype "bidirectional"))
      (node (ref "U4") (pin "14") (pinfunction "VCC_14") (pintype "bidirectional"))
      (node (ref "U5") (pin "14") (pinfunction "VCC_14") (pintype "bidirectional"))
      (node (ref "U6") (pin "14") (pinfunction "VCC_14") (pintype "bidirectional"))
      (node (ref "U7") (pin "8") (pinfunction "VCC_8") (pintype "power_in"))
      (node (ref "U8") (pin "14") (pinfunction "VCC_14") (pintype "bidirectional"))
      (node (ref "U9") (pin "14") (pinfunction "VCC_14") (pintype "bidirectional"))
      (node (ref "USB") (pin "5") (pinfunction "5_5") (pintype "bidirectional"))
    )
    (net (code "222") (name "unconnected-(H1-Pad1)") (class "Default")
      (node (ref "H1") (pin "1") (pinfunction "1_1") (pintype "bidirectional"))
    )
    (net (code "223") (name "unconnected-(H1-Pad2)") (class "Default")
      (node (ref "H1") (pin "2") (pinfunction "2_2") (pintype "bidirectional"))
    )
    (net (code "224") (name "unconnected-(H2-Pad5)") (class "Default")
      (node (ref "H2") (pin "5") (pinfunction "5_5") (pintype "bidirectional"))
    )
    (net (code "225") (name "unconnected-(H2-Pad7)") (class "Default")
      (node (ref "H2") (pin "7") (pinfunction "7_7") (pintype "bidirectional"))
    )
    (net (code "226") (name "unconnected-(H3-Pad2)") (class "Default")
      (node (ref "H3") (pin "2") (pinfunction "2_2") (pintype "bidirectional"))
    )
    (net (code "227") (name "unconnected-(H3-Pad4)") (class "Default")
      (node (ref "H3") (pin "4") (pinfunction "4_4") (pintype "bidirectional"))
    )
    (net (code "228") (name "unconnected-(H3-Pad6)") (class "Default")
      (node (ref "H3") (pin "6") (pinfunction "6_6") (pintype "bidirectional"))
    )
    (net (code "229") (name "unconnected-(H3-Pad8)") (class "Default")
      (node (ref "H3") (pin "8") (pinfunction "8_8") (pintype "bidirectional"))
    )
    (net (code "230") (name "unconnected-(H5-Pad14)") (class "Default")
      (node (ref "H5") (pin "14") (pinfunction "14_14") (pintype "bidirectional"))
    )
    (net (code "231") (name "unconnected-(H5-Pad16)") (class "Default")
      (node (ref "H5") (pin "16") (pinfunction "16_16") (pintype "bidirectional"))
    )
    (net (code "232") (name "unconnected-(H5-Pad18)") (class "Default")
      (node (ref "H5") (pin "18") (pinfunction "18_18") (pintype "bidirectional"))
    )
    (net (code "233") (name "unconnected-(H7-Pad1)") (class "Default")
      (node (ref "H7") (pin "1") (pinfunction "1_1") (pintype "bidirectional"))
    )
    (net (code "234") (name "unconnected-(H7-Pad2)") (class "Default")
      (node (ref "H7") (pin "2") (pinfunction "2_2") (pintype "bidirectional"))
    )
    (net (code "235") (name "unconnected-(IC3-NC-Pad4)") (class "Default")
      (node (ref "IC3") (pin "4") (pinfunction "NC_4") (pintype "no_connect"))
    )
    (net (code "236") (name "unconnected-(USB-Pad2)") (class "Default")
      (node (ref "USB") (pin "2") (pinfunction "2_2") (pintype "bidirectional"))
    )
    (net (code "237") (name "unconnected-(USB-Pad3)") (class "Default")
      (node (ref "USB") (pin "3") (pinfunction "3_3") (pintype "bidirectional"))
    )
    (net (code "238") (name "unconnected-(USB-Pad4)") (class "Default")
      (node (ref "USB") (pin "4") (pinfunction "4_4") (pintype "bidirectional"))
    )
  )
)
